# Pinscape_Pico_Expansion_Board_-_DIY_Frie.net
KiCad netlist of a schematic drawn in EAGLE
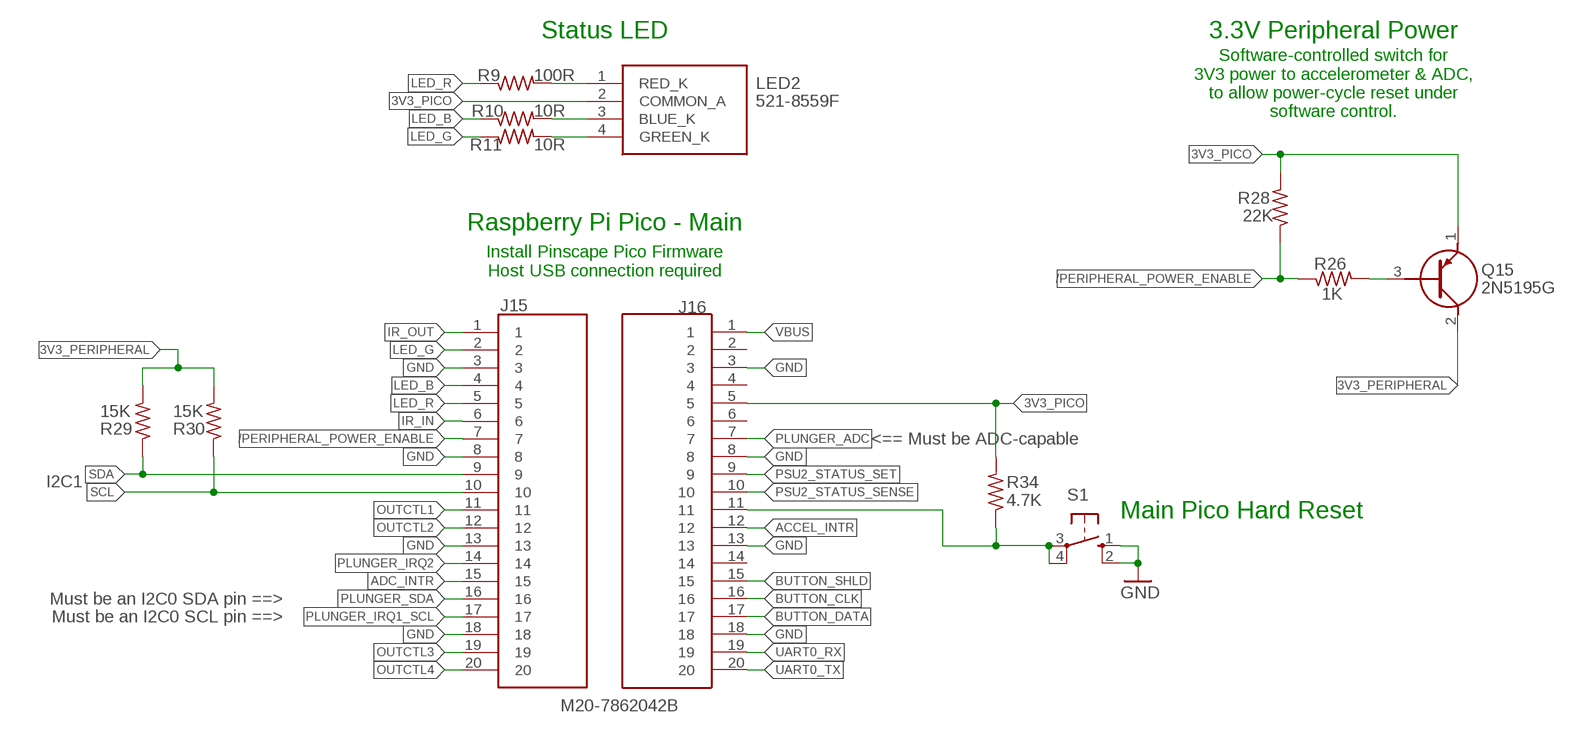
[diagram p0: schematic, sheet 1]
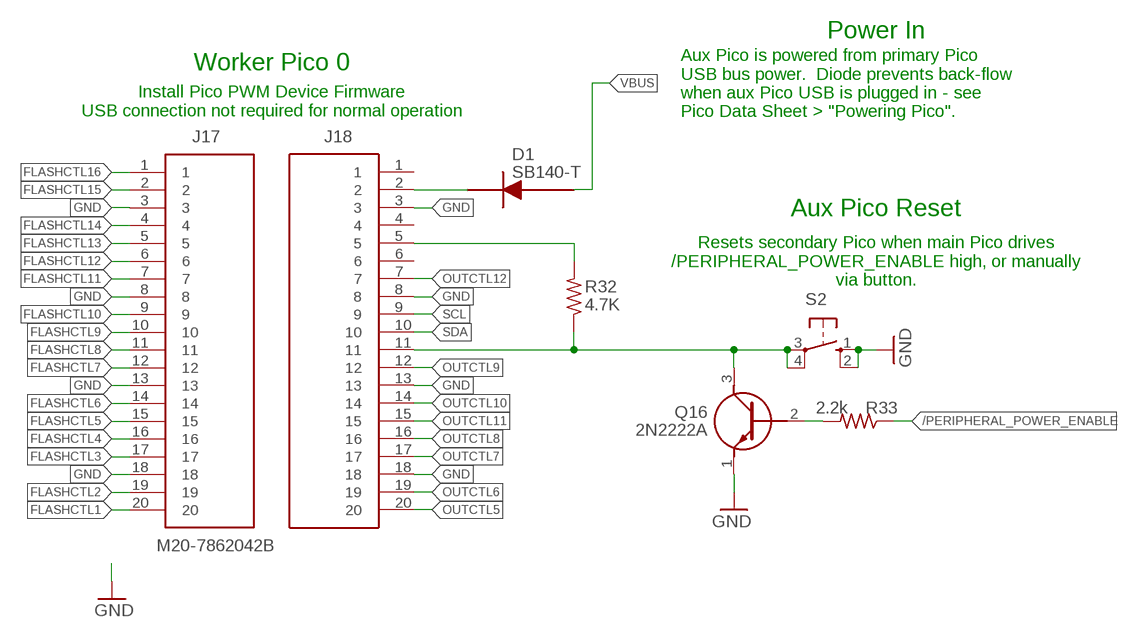
[diagram p1: schematic, sheet 2]
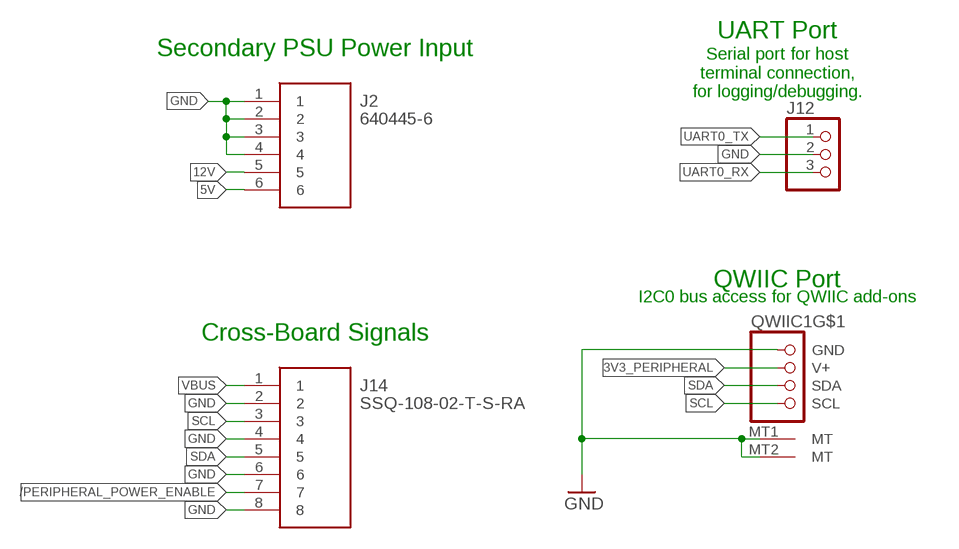
[diagram p2: schematic, sheet 3]
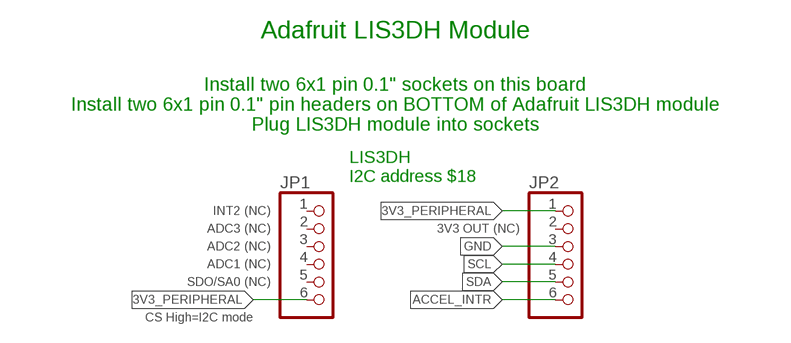
[diagram p3: schematic, sheet 4]
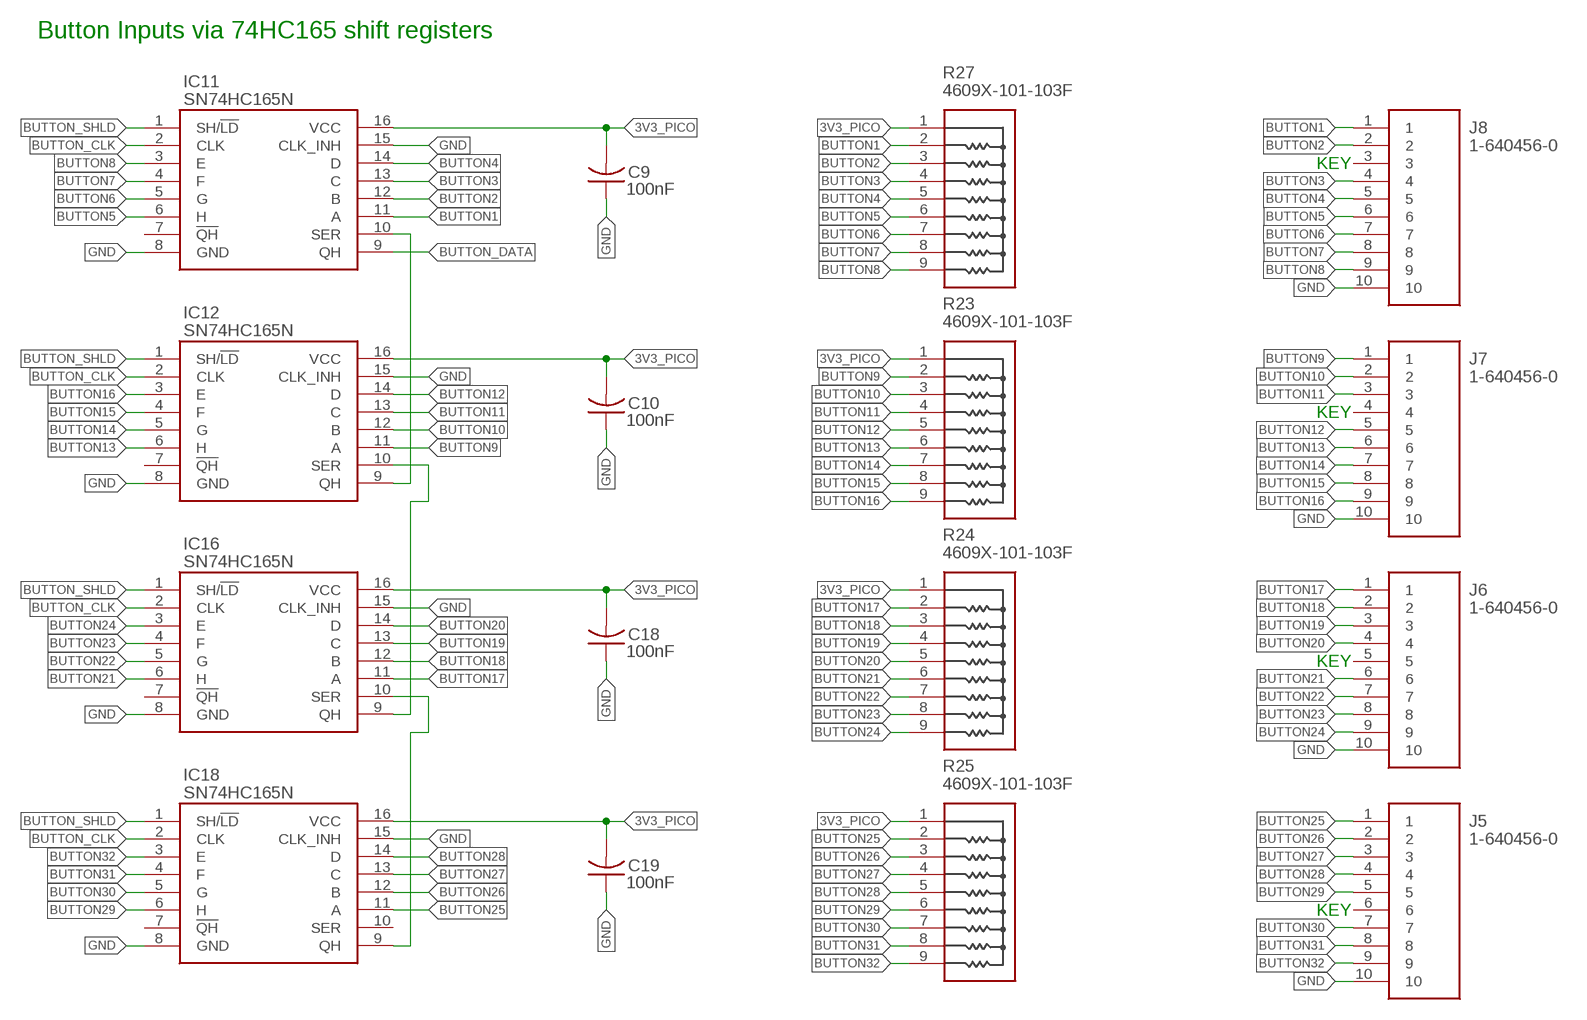
[diagram p4: schematic, sheet 5]
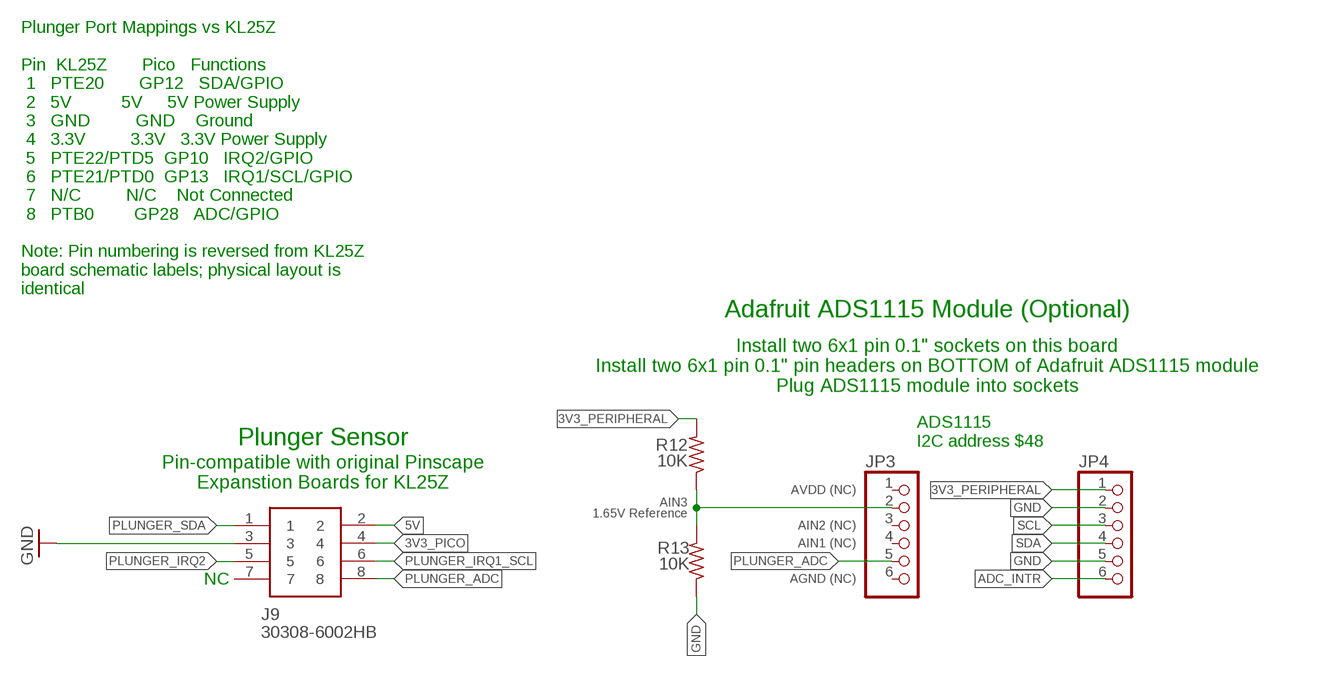
[diagram p5: schematic, sheet 6]
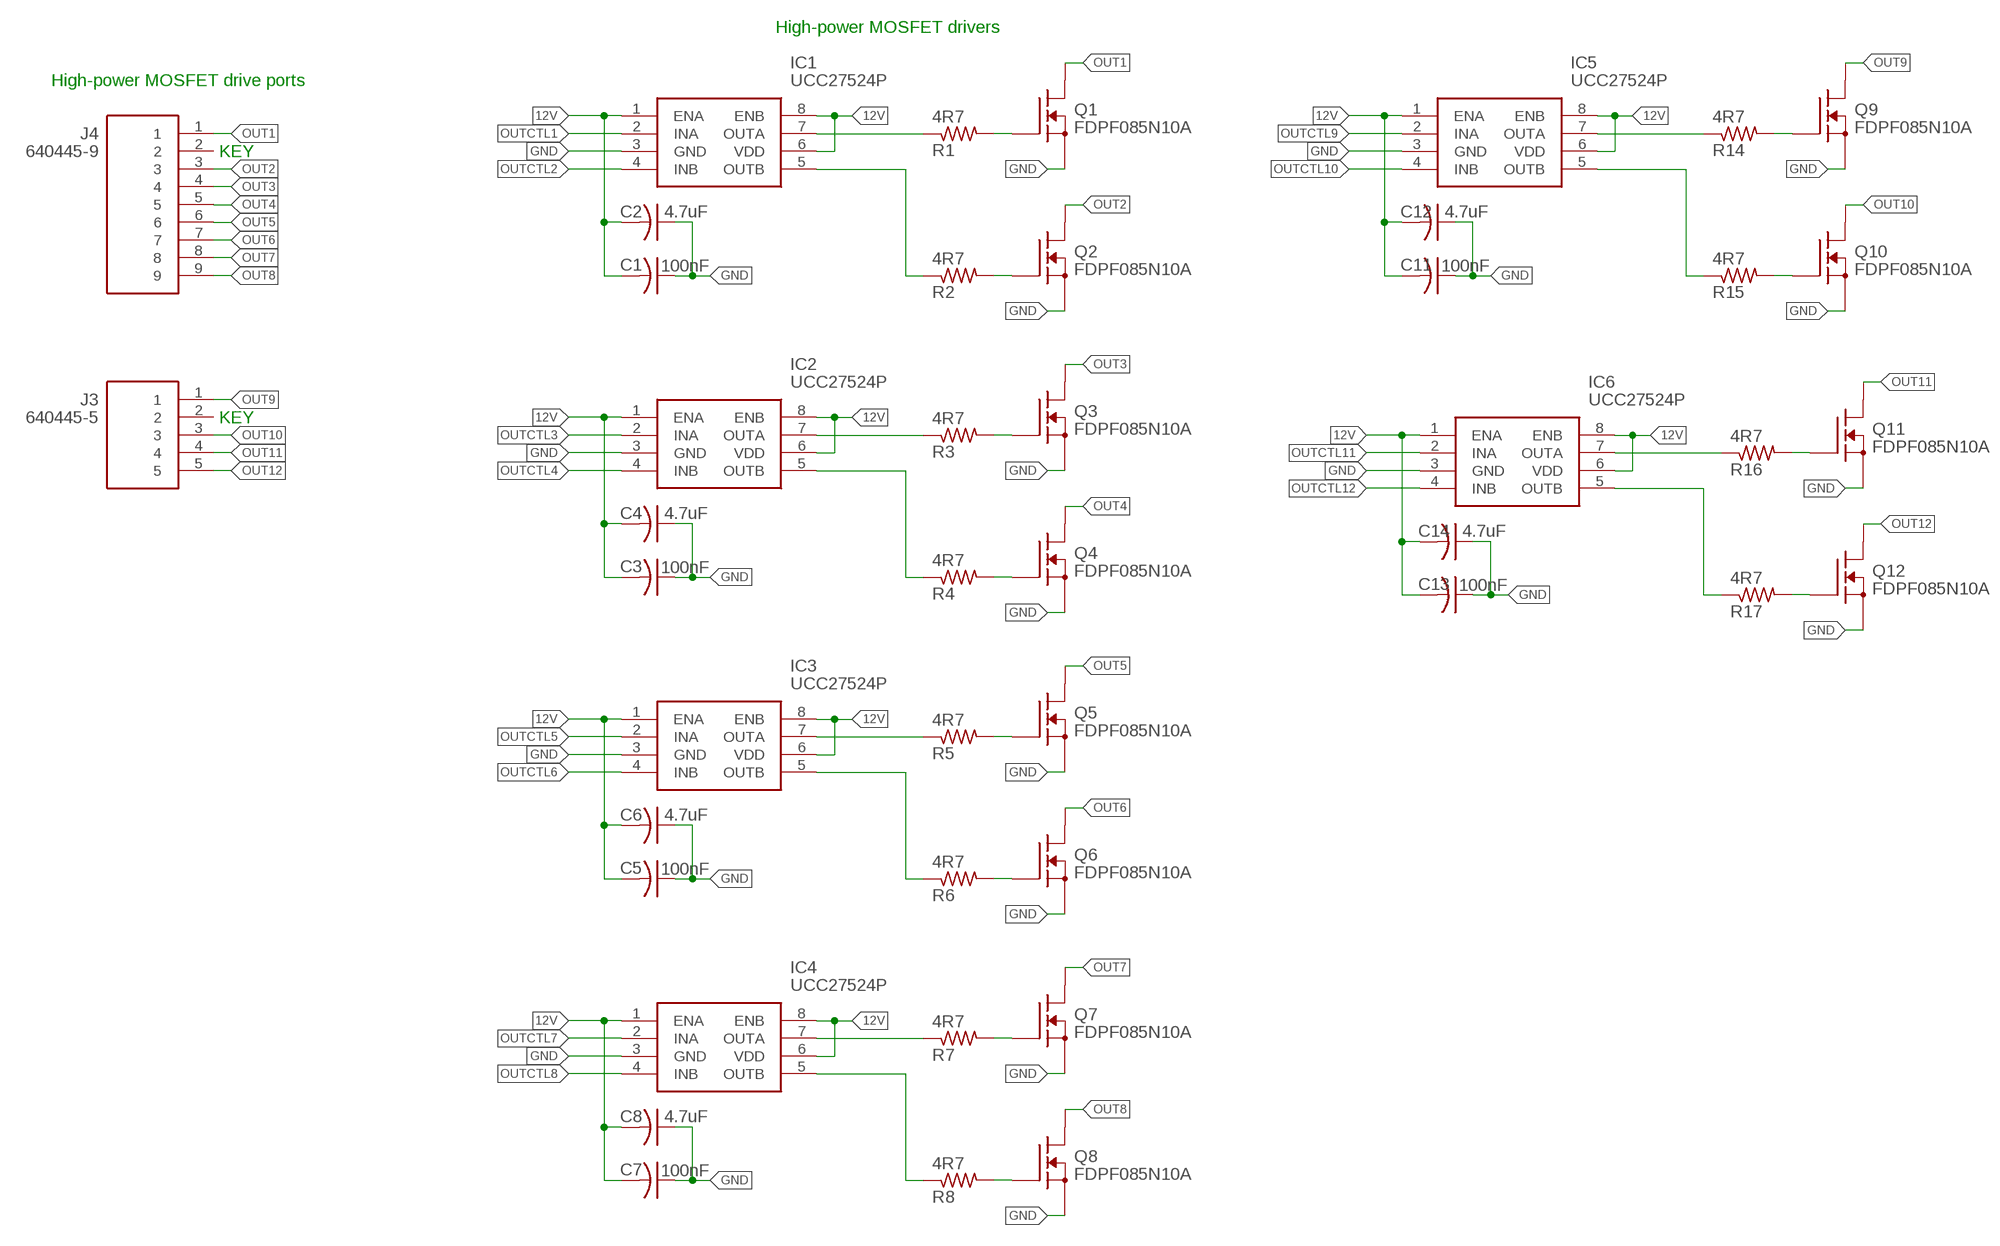
[diagram p6: schematic, sheet 7]
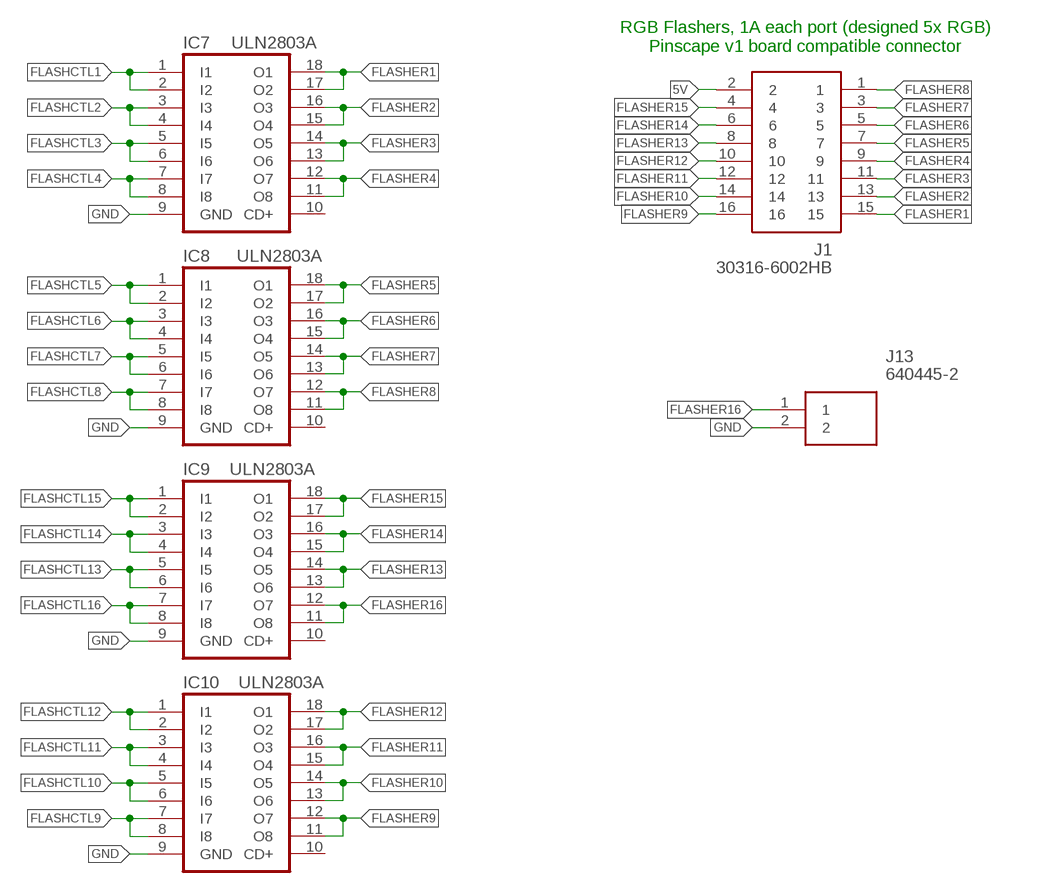
[diagram p7: schematic, sheet 8]
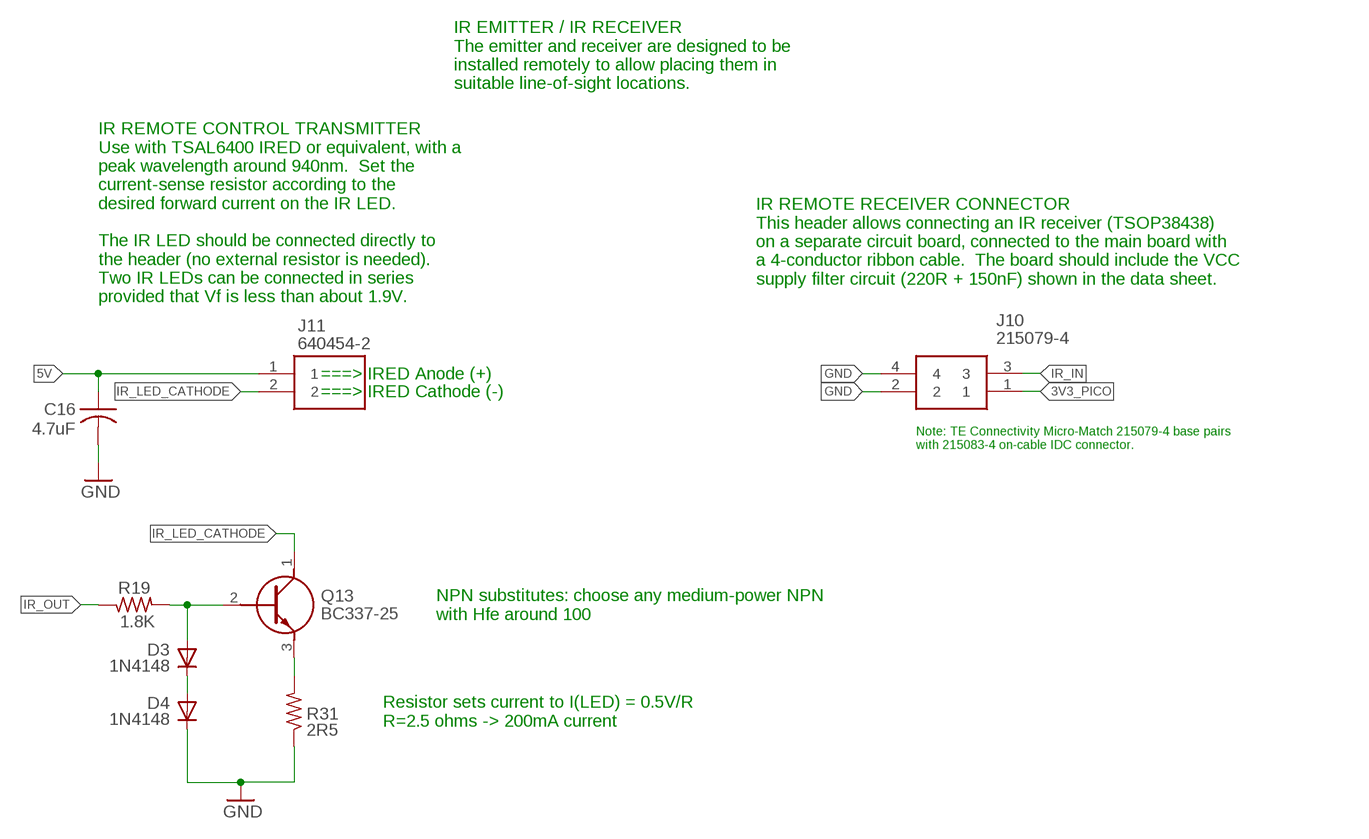
[diagram p8: schematic, sheet 9]
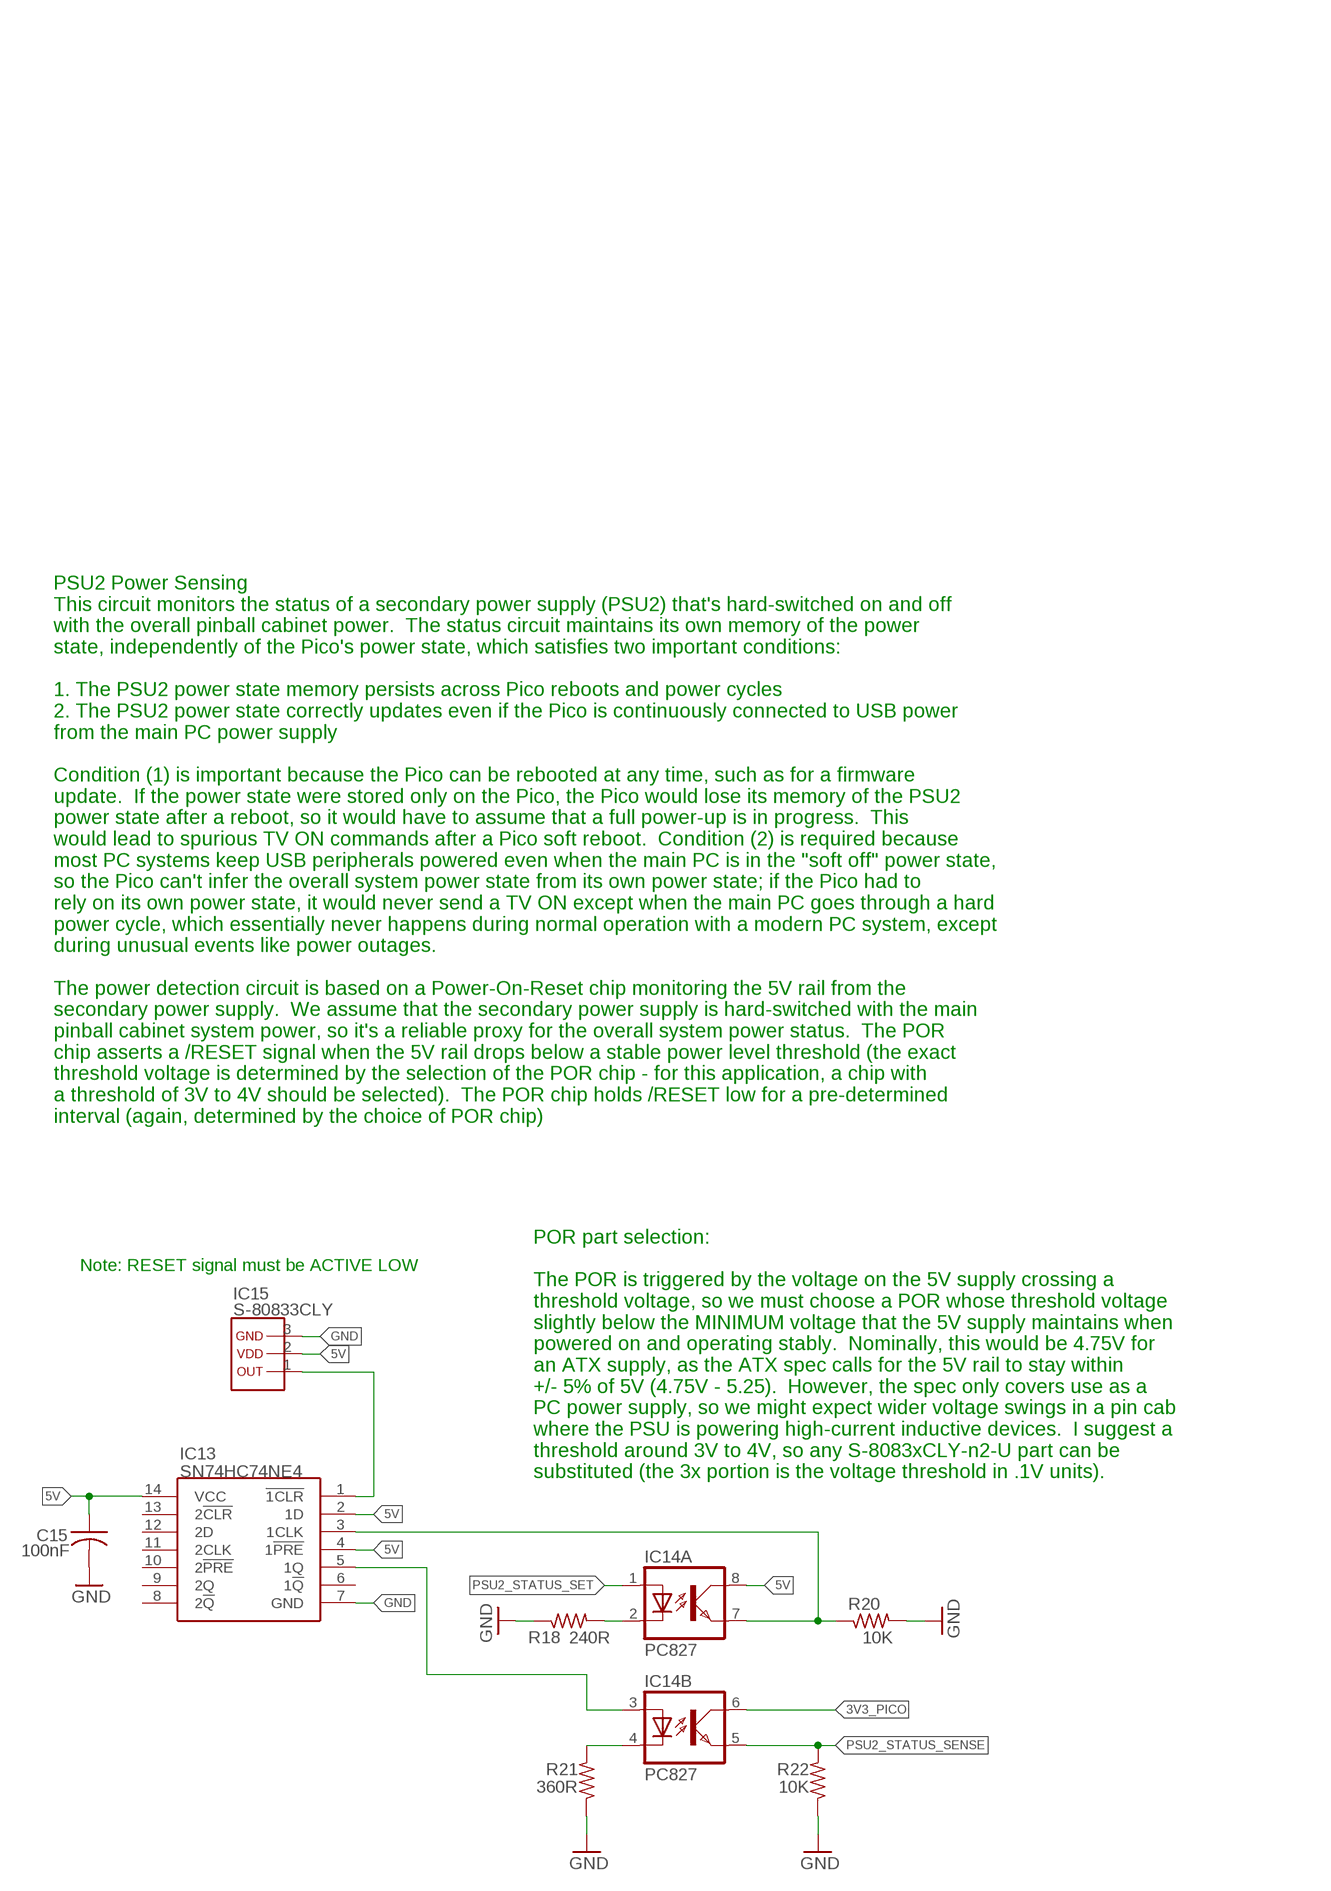
[diagram p9: schematic, sheet 10]
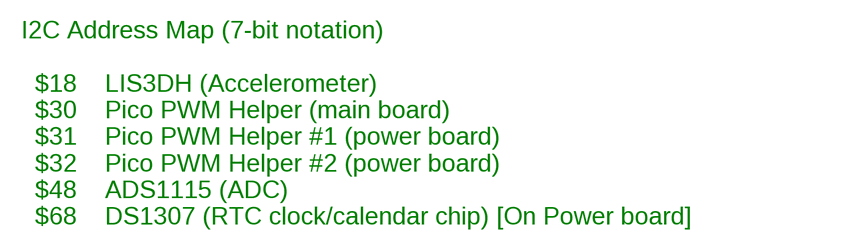
[diagram p10: schematic, sheet 11]

(export (version "E")
  (design (tool "Eeschema 10.0.6"))
  (components
    (comp (ref "JP1")
      (value "PINHD-1X6")
      (footprint "eagle-import:1X06")
      (libsource (lib "eagle-import") (part "PINHD-1X6"))
    )
    (comp (ref "JP2")
      (value "PINHD-1X6")
      (footprint "eagle-import:1X06")
      (libsource (lib "eagle-import") (part "PINHD-1X6"))
    )
    (comp (ref "J15")
      (value "M20-7862042B")
      (footprint "eagle-import:M20-7862042-B")
      (libsource (lib "eagle-import") (part "M20-7862042B"))
    )
    (comp (ref "J16")
      (value "M20-7862042B")
      (footprint "eagle-import:M20-7862042-B")
      (libsource (lib "eagle-import") (part "M20-7862042B"))
    )
    (comp (ref "LED2")
      (value "521-8559F")
      (footprint "eagle-import:5218559F")
      (fields (field (name "MOUSER_PART_NUMBER") "645-5218559F"))
      (libsource (lib "eagle-import") (part "521-8559F"))
    )
    (comp (ref "Q15")
      (value "2N5195G")
      (footprint "eagle-import:TO229P300X760X1364-3P")
      (fields (field (name "MOUSER_PART_NUMBER") "863-2N5195G"))
      (libsource (lib "eagle-import") (part "2N5195G"))
    )
    (comp (ref "R9")
      (value "100R")
      (footprint "eagle-import:0204_7")
      (fields (field (name "PARTNO") "660-MFS1/4DCT52R47R0"))
      (libsource (lib "eagle-import") (part "R-US_0204/7"))
    )
    (comp (ref "R10")
      (value "10R")
      (footprint "eagle-import:0204_7")
      (fields (field (name "PARTNO") "660-MFS1/4DCT52R47R0"))
      (libsource (lib "eagle-import") (part "R-US_0204/7"))
    )
    (comp (ref "R11")
      (value "10R")
      (footprint "eagle-import:0204_7")
      (fields (field (name "PARTNO") "660-MFS1/4DCT52R47R0"))
      (libsource (lib "eagle-import") (part "R-US_0204/7"))
    )
    (comp (ref "R26")
      (value "1K")
      (footprint "eagle-import:0204_7")
      (fields (field (name "PARTNO") "660-MFS1/4DCT52R47R0"))
      (libsource (lib "eagle-import") (part "R-US_0204/7"))
    )
    (comp (ref "R28")
      (value "22K")
      (footprint "eagle-import:0204_7")
      (fields (field (name "PARTNO") "660-MFS1/4DCT52R47R0"))
      (libsource (lib "eagle-import") (part "R-US_0204/7"))
    )
    (comp (ref "R29")
      (value "15K")
      (footprint "eagle-import:0204_7")
      (fields (field (name "PARTNO") "660-MFS1/4DCT52R47R0"))
      (libsource (lib "eagle-import") (part "R-US_0204/7"))
    )
    (comp (ref "R30")
      (value "15K")
      (footprint "eagle-import:0204_7")
      (fields (field (name "PARTNO") "660-MFS1/4DCT52R47R0"))
      (libsource (lib "eagle-import") (part "R-US_0204/7"))
    )
    (comp (ref "R34")
      (value "4.7K")
      (footprint "eagle-import:0204_7")
      (fields (field (name "PARTNO") "660-MFS1/4DCT52R47R0"))
      (libsource (lib "eagle-import") (part "R-US_0204/7"))
    )
    (comp (ref "S1")
      (value "10-XX")
      (footprint "eagle-import:B3F-10XX")
      (fields (field (name "MPN") "B3F-1000"))
      (libsource (lib "eagle-import") (part "10-XX"))
    )
    (comp (ref "J2")
      (value "640445-6")
      (footprint "eagle-import:SHDR6W183P0X396_1X6_2377X762X1")
      (fields (field (name "MOUSER_PART_NUMBER") "571-6404456"))
      (libsource (lib "eagle-import") (part "640445-6"))
    )
    (comp (ref "J12")
      (value "PINHD-1X3")
      (footprint "eagle-import:1X03")
      (libsource (lib "eagle-import") (part "PINHD-1X3"))
    )
    (comp (ref "J14")
      (value "SSQ-108-02-T-S-RA")
      (footprint "eagle-import:RHDRRA8W64P254_1X8_2083X851X24")
      (fields (field (name "MOUSER_PART_NUMBER") "200-SSQ10802TSRA"))
      (libsource (lib "eagle-import") (part "SSQ-108-02-T-S-RA"))
    )
    (comp (ref "QWIIC1")
      (value "QWIIC")
      (footprint "eagle-import:JST_SH4")
      (libsource (lib "eagle-import") (part "STEMMA_I2C_QT"))
    )
    (comp (ref "D1")
      (value "SB140-T")
      (footprint "eagle-import:DIOAD1408W86L464D236")
      (fields (field (name "MOUSER_PART_NUMBER") "621-SB140-T"))
      (libsource (lib "eagle-import") (part "SB140-T"))
    )
    (comp (ref "J17")
      (value "M20-7862042B")
      (footprint "eagle-import:M20-7862042-B")
      (libsource (lib "eagle-import") (part "M20-7862042B"))
    )
    (comp (ref "J18")
      (value "M20-7862042B")
      (footprint "eagle-import:M20-7862042-B")
      (libsource (lib "eagle-import") (part "M20-7862042B"))
    )
    (comp (ref "Q16")
      (value "2N2222A")
      (footprint "eagle-import:2N2222A")
      (fields (field (name "MOUSER_PART_NUMBER") "637-2N2222A"))
      (libsource (lib "eagle-import") (part "2N2222A"))
    )
    (comp (ref "R32")
      (value "4.7K")
      (footprint "eagle-import:0204_7")
      (fields (field (name "PARTNO") "660-MFS1/4DCT52R47R0"))
      (libsource (lib "eagle-import") (part "R-US_0204/7"))
    )
    (comp (ref "R33")
      (value "2.2k")
      (footprint "eagle-import:0204_7")
      (fields (field (name "PARTNO") "660-MFS1/4DCT52R47R0"))
      (libsource (lib "eagle-import") (part "R-US_0204/7"))
    )
    (comp (ref "S2")
      (value "10-XX")
      (footprint "eagle-import:B3F-10XX")
      (fields (field (name "MPN") "B3F-1000"))
      (libsource (lib "eagle-import") (part "10-XX"))
    )
    (comp (ref "IC7")
      (value "ULN2803A")
      (footprint "eagle-import:DIL18")
      (libsource (lib "eagle-import") (part "ULN2803A"))
    )
    (comp (ref "IC8")
      (value "ULN2803A")
      (footprint "eagle-import:DIL18")
      (libsource (lib "eagle-import") (part "ULN2803A"))
    )
    (comp (ref "IC9")
      (value "ULN2803A")
      (footprint "eagle-import:DIL18")
      (libsource (lib "eagle-import") (part "ULN2803A"))
    )
    (comp (ref "IC10")
      (value "ULN2803A")
      (footprint "eagle-import:DIL18")
      (libsource (lib "eagle-import") (part "ULN2803A"))
    )
    (comp (ref "J1")
      (value "30316-6002HB")
      (footprint "eagle-import:3M-30316-6002HB")
      (fields (field (name "MOUSER_PART_NUMBER") "517-30316-6002"))
      (libsource (lib "eagle-import") (part "30316-6002HB"))
    )
    (comp (ref "J13")
      (value "640445-2")
      (footprint "eagle-import:SHDR2W117P0X396_1X2_792X762X11")
      (fields (field (name "MOUSER_PART_NUMBER") "5716404452"))
      (libsource (lib "eagle-import") (part "640445-2"))
    )
    (comp (ref "C1")
      (value "100nF")
      (footprint "eagle-import:C025-024X044")
      (fields (field (name "PARTNO") "21RZ310-RC"))
      (libsource (lib "eagle-import") (part "C-US025-024X044"))
    )
    (comp (ref "C2")
      (value "4.7uF")
      (footprint "eagle-import:C025-024X044")
      (fields (field (name "PARTNO") "810-FG14X5R1H475KRT0"))
      (libsource (lib "eagle-import") (part "C-US025-024X044"))
    )
    (comp (ref "C3")
      (value "100nF")
      (footprint "eagle-import:C025-024X044")
      (fields (field (name "PARTNO") "21RZ310-RC"))
      (libsource (lib "eagle-import") (part "C-US025-024X044"))
    )
    (comp (ref "C4")
      (value "4.7uF")
      (footprint "eagle-import:C025-024X044")
      (fields (field (name "PARTNO") "810-FG14X5R1H475KRT0"))
      (libsource (lib "eagle-import") (part "C-US025-024X044"))
    )
    (comp (ref "C5")
      (value "100nF")
      (footprint "eagle-import:C025-024X044")
      (fields (field (name "PARTNO") "21RZ310-RC"))
      (libsource (lib "eagle-import") (part "C-US025-024X044"))
    )
    (comp (ref "C6")
      (value "4.7uF")
      (footprint "eagle-import:C025-024X044")
      (fields (field (name "PARTNO") "810-FG14X5R1H475KRT0"))
      (libsource (lib "eagle-import") (part "C-US025-024X044"))
    )
    (comp (ref "C7")
      (value "100nF")
      (footprint "eagle-import:C025-024X044")
      (fields (field (name "PARTNO") "21RZ310-RC"))
      (libsource (lib "eagle-import") (part "C-US025-024X044"))
    )
    (comp (ref "C8")
      (value "4.7uF")
      (footprint "eagle-import:C025-024X044")
      (fields (field (name "PARTNO") "810-FG14X5R1H475KRT0"))
      (libsource (lib "eagle-import") (part "C-US025-024X044"))
    )
    (comp (ref "C11")
      (value "100nF")
      (footprint "eagle-import:C025-024X044")
      (fields (field (name "PARTNO") "21RZ310-RC"))
      (libsource (lib "eagle-import") (part "C-US025-024X044"))
    )
    (comp (ref "C12")
      (value "4.7uF")
      (footprint "eagle-import:C025-024X044")
      (fields (field (name "PARTNO") "810-FG14X5R1H475KRT0"))
      (libsource (lib "eagle-import") (part "C-US025-024X044"))
    )
    (comp (ref "C13")
      (value "100nF")
      (footprint "eagle-import:C025-024X044")
      (fields (field (name "PARTNO") "21RZ310-RC"))
      (libsource (lib "eagle-import") (part "C-US025-024X044"))
    )
    (comp (ref "C14")
      (value "4.7uF")
      (footprint "eagle-import:C025-024X044")
      (fields (field (name "PARTNO") "810-FG14X5R1H475KRT0"))
      (libsource (lib "eagle-import") (part "C-US025-024X044"))
    )
    (comp (ref "IC1")
      (value "UCC27524P")
      (footprint "eagle-import:DIP794W53P254L959H508Q8N")
      (fields (field (name "MOUSER_PART_NUMBER") "595-UCC27524P"))
      (libsource (lib "eagle-import") (part "UCC27524P"))
    )
    (comp (ref "IC2")
      (value "UCC27524P")
      (footprint "eagle-import:DIP794W53P254L959H508Q8N")
      (fields (field (name "MOUSER_PART_NUMBER") "595-UCC27524P"))
      (libsource (lib "eagle-import") (part "UCC27524P"))
    )
    (comp (ref "IC3")
      (value "UCC27524P")
      (footprint "eagle-import:DIP794W53P254L959H508Q8N")
      (fields (field (name "MOUSER_PART_NUMBER") "595-UCC27524P"))
      (libsource (lib "eagle-import") (part "UCC27524P"))
    )
    (comp (ref "IC4")
      (value "UCC27524P")
      (footprint "eagle-import:DIP794W53P254L959H508Q8N")
      (fields (field (name "MOUSER_PART_NUMBER") "595-UCC27524P"))
      (libsource (lib "eagle-import") (part "UCC27524P"))
    )
    (comp (ref "IC5")
      (value "UCC27524P")
      (footprint "eagle-import:DIP794W53P254L959H508Q8N")
      (fields (field (name "MOUSER_PART_NUMBER") "595-UCC27524P"))
      (libsource (lib "eagle-import") (part "UCC27524P"))
    )
    (comp (ref "IC6")
      (value "UCC27524P")
      (footprint "eagle-import:DIP794W53P254L959H508Q8N")
      (fields (field (name "MOUSER_PART_NUMBER") "595-UCC27524P"))
      (libsource (lib "eagle-import") (part "UCC27524P"))
    )
    (comp (ref "J3")
      (value "640445-5")
      (footprint "eagle-import:HDRV5W117P0X396_1X5_1981X762X1")
      (fields (field (name "MOUSER_PART_NUMBER") "571-640445-5"))
      (libsource (lib "eagle-import") (part "640445-5"))
    )
    (comp (ref "J4")
      (value "640445-9")
      (footprint "eagle-import:SHDR9W117P0X396_1X9_3566X762X1")
      (fields (field (name "MOUSER_PART_NUMBER") "571-6404459"))
      (libsource (lib "eagle-import") (part "640445-9"))
    )
    (comp (ref "Q1")
      (value "FDPF085N10A")
      (footprint "eagle-import:TO220BV")
      (fields (field (name "PARTNO") "FDPF085N10A"))
      (libsource (lib "eagle-import") (part "BUK7575-55A"))
    )
    (comp (ref "Q2")
      (value "FDPF085N10A")
      (footprint "eagle-import:TO220BV")
      (fields (field (name "PARTNO") "FDPF085N10A"))
      (libsource (lib "eagle-import") (part "BUK7575-55A"))
    )
    (comp (ref "Q3")
      (value "FDPF085N10A")
      (footprint "eagle-import:TO220BV")
      (fields (field (name "PARTNO") "FDPF085N10A"))
      (libsource (lib "eagle-import") (part "BUK7575-55A"))
    )
    (comp (ref "Q4")
      (value "FDPF085N10A")
      (footprint "eagle-import:TO220BV")
      (fields (field (name "PARTNO") "FDPF085N10A"))
      (libsource (lib "eagle-import") (part "BUK7575-55A"))
    )
    (comp (ref "Q5")
      (value "FDPF085N10A")
      (footprint "eagle-import:TO220BV")
      (fields (field (name "PARTNO") "FDPF085N10A"))
      (libsource (lib "eagle-import") (part "BUK7575-55A"))
    )
    (comp (ref "Q6")
      (value "FDPF085N10A")
      (footprint "eagle-import:TO220BV")
      (fields (field (name "PARTNO") "FDPF085N10A"))
      (libsource (lib "eagle-import") (part "BUK7575-55A"))
    )
    (comp (ref "Q7")
      (value "FDPF085N10A")
      (footprint "eagle-import:TO220BV")
      (fields (field (name "PARTNO") "FDPF085N10A"))
      (libsource (lib "eagle-import") (part "BUK7575-55A"))
    )
    (comp (ref "Q8")
      (value "FDPF085N10A")
      (footprint "eagle-import:TO220BV")
      (fields (field (name "PARTNO") "FDPF085N10A"))
      (libsource (lib "eagle-import") (part "BUK7575-55A"))
    )
    (comp (ref "Q9")
      (value "FDPF085N10A")
      (footprint "eagle-import:TO220BV")
      (fields (field (name "PARTNO") "FDPF085N10A"))
      (libsource (lib "eagle-import") (part "BUK7575-55A"))
    )
    (comp (ref "Q10")
      (value "FDPF085N10A")
      (footprint "eagle-import:TO220BV")
      (fields (field (name "PARTNO") "FDPF085N10A"))
      (libsource (lib "eagle-import") (part "BUK7575-55A"))
    )
    (comp (ref "Q11")
      (value "FDPF085N10A")
      (footprint "eagle-import:TO220BV")
      (fields (field (name "PARTNO") "FDPF085N10A"))
      (libsource (lib "eagle-import") (part "BUK7575-55A"))
    )
    (comp (ref "Q12")
      (value "FDPF085N10A")
      (footprint "eagle-import:TO220BV")
      (fields (field (name "PARTNO") "FDPF085N10A"))
      (libsource (lib "eagle-import") (part "BUK7575-55A"))
    )
    (comp (ref "R1")
      (value "4R7")
      (footprint "eagle-import:0204_5")
      (fields (field (name "PARTNO") "660-MFS1/4DCT52R47R0"))
      (libsource (lib "eagle-import") (part "R-US_0204/5"))
    )
    (comp (ref "R2")
      (value "4R7")
      (footprint "eagle-import:0204_5")
      (fields (field (name "PARTNO") "660-MFS1/4DCT52R47R0"))
      (libsource (lib "eagle-import") (part "R-US_0204/5"))
    )
    (comp (ref "R3")
      (value "4R7")
      (footprint "eagle-import:0204_5")
      (fields (field (name "PARTNO") "660-MFS1/4DCT52R47R0"))
      (libsource (lib "eagle-import") (part "R-US_0204/5"))
    )
    (comp (ref "R4")
      (value "4R7")
      (footprint "eagle-import:0204_5")
      (fields (field (name "PARTNO") "660-MFS1/4DCT52R47R0"))
      (libsource (lib "eagle-import") (part "R-US_0204/5"))
    )
    (comp (ref "R5")
      (value "4R7")
      (footprint "eagle-import:0204_5")
      (fields (field (name "PARTNO") "660-MFS1/4DCT52R47R0"))
      (libsource (lib "eagle-import") (part "R-US_0204/5"))
    )
    (comp (ref "R6")
      (value "4R7")
      (footprint "eagle-import:0204_5")
      (fields (field (name "PARTNO") "660-MFS1/4DCT52R47R0"))
      (libsource (lib "eagle-import") (part "R-US_0204/5"))
    )
    (comp (ref "R7")
      (value "4R7")
      (footprint "eagle-import:0204_5")
      (fields (field (name "PARTNO") "660-MFS1/4DCT52R47R0"))
      (libsource (lib "eagle-import") (part "R-US_0204/5"))
    )
    (comp (ref "R8")
      (value "4R7")
      (footprint "eagle-import:0204_5")
      (fields (field (name "PARTNO") "660-MFS1/4DCT52R47R0"))
      (libsource (lib "eagle-import") (part "R-US_0204/5"))
    )
    (comp (ref "R14")
      (value "4R7")
      (footprint "eagle-import:0204_5")
      (fields (field (name "PARTNO") "660-MFS1/4DCT52R47R0"))
      (libsource (lib "eagle-import") (part "R-US_0204/5"))
    )
    (comp (ref "R15")
      (value "4R7")
      (footprint "eagle-import:0204_5")
      (fields (field (name "PARTNO") "660-MFS1/4DCT52R47R0"))
      (libsource (lib "eagle-import") (part "R-US_0204/5"))
    )
    (comp (ref "R16")
      (value "4R7")
      (footprint "eagle-import:0204_5")
      (fields (field (name "PARTNO") "660-MFS1/4DCT52R47R0"))
      (libsource (lib "eagle-import") (part "R-US_0204/5"))
    )
    (comp (ref "R17")
      (value "4R7")
      (footprint "eagle-import:0204_5")
      (fields (field (name "PARTNO") "660-MFS1/4DCT52R47R0"))
      (libsource (lib "eagle-import") (part "R-US_0204/5"))
    )
    (comp (ref "C9")
      (value "100nF")
      (footprint "eagle-import:C025-024X044")
      (fields (field (name "PARTNO") "21RZ310-RC"))
      (libsource (lib "eagle-import") (part "C-US025-024X044"))
    )
    (comp (ref "C10")
      (value "100nF")
      (footprint "eagle-import:C025-024X044")
      (fields (field (name "PARTNO") "21RZ310-RC"))
      (libsource (lib "eagle-import") (part "C-US025-024X044"))
    )
    (comp (ref "C18")
      (value "100nF")
      (footprint "eagle-import:C025-024X044")
      (fields (field (name "PARTNO") "21RZ310-RC"))
      (libsource (lib "eagle-import") (part "C-US025-024X044"))
    )
    (comp (ref "C19")
      (value "100nF")
      (footprint "eagle-import:C025-024X044")
      (fields (field (name "PARTNO") "21RZ310-RC"))
      (libsource (lib "eagle-import") (part "C-US025-024X044"))
    )
    (comp (ref "IC11")
      (value "SN74HC165N")
      (footprint "eagle-import:DIP794W53P254L1930H508Q16N")
      (fields (field (name "MOUSER_PART_NUMBER") "595-SN74HC165N"))
      (libsource (lib "eagle-import") (part "SN74HC165N"))
    )
    (comp (ref "IC12")
      (value "SN74HC165N")
      (footprint "eagle-import:DIP794W53P254L1930H508Q16N")
      (fields (field (name "MOUSER_PART_NUMBER") "595-SN74HC165N"))
      (libsource (lib "eagle-import") (part "SN74HC165N"))
    )
    (comp (ref "IC16")
      (value "SN74HC165N")
      (footprint "eagle-import:DIP794W53P254L1930H508Q16N")
      (fields (field (name "MOUSER_PART_NUMBER") "595-SN74HC165N"))
      (libsource (lib "eagle-import") (part "SN74HC165N"))
    )
    (comp (ref "IC18")
      (value "SN74HC165N")
      (footprint "eagle-import:DIP794W53P254L1930H508Q16N")
      (fields (field (name "MOUSER_PART_NUMBER") "595-SN74HC165N"))
      (libsource (lib "eagle-import") (part "SN74HC165N"))
    )
    (comp (ref "J5")
      (value "1-640456-0")
      (footprint "eagle-import:SHDR10W66P0X254_1X10_2540X572X")
      (fields (field (name "MOUSER_PART_NUMBER") "571-16404560"))
      (libsource (lib "eagle-import") (part "1-640456-0"))
    )
    (comp (ref "J6")
      (value "1-640456-0")
      (footprint "eagle-import:SHDR10W66P0X254_1X10_2540X572X")
      (fields (field (name "MOUSER_PART_NUMBER") "571-16404560"))
      (libsource (lib "eagle-import") (part "1-640456-0"))
    )
    (comp (ref "J7")
      (value "1-640456-0")
      (footprint "eagle-import:SHDR10W66P0X254_1X10_2540X572X")
      (fields (field (name "MOUSER_PART_NUMBER") "571-16404560"))
      (libsource (lib "eagle-import") (part "1-640456-0"))
    )
    (comp (ref "J8")
      (value "1-640456-0")
      (footprint "eagle-import:SHDR10W66P0X254_1X10_2540X572X")
      (fields (field (name "MOUSER_PART_NUMBER") "571-16404560"))
      (libsource (lib "eagle-import") (part "1-640456-0"))
    )
    (comp (ref "R23")
      (value "4609X-101-103F")
      (footprint "eagle-import:4609X")
      (fields
        (field (name "MANUFACTURER_PART_NUMBER") "4609X-101-122LF")
        (field (name "MOUSER_PART_NUMBER") "652-4609X-1LF-1.2K")
      )
      (libsource (lib "eagle-import") (part "4609X-101-122LF"))
    )
    (comp (ref "R24")
      (value "4609X-101-103F")
      (footprint "eagle-import:4609X")
      (fields
        (field (name "MANUFACTURER_PART_NUMBER") "4609X-101-122LF")
        (field (name "MOUSER_PART_NUMBER") "652-4609X-1LF-1.2K")
      )
      (libsource (lib "eagle-import") (part "4609X-101-122LF"))
    )
    (comp (ref "R25")
      (value "4609X-101-103F")
      (footprint "eagle-import:4609X")
      (fields
        (field (name "MANUFACTURER_PART_NUMBER") "4609X-101-122LF")
        (field (name "MOUSER_PART_NUMBER") "652-4609X-1LF-1.2K")
      )
      (libsource (lib "eagle-import") (part "4609X-101-122LF"))
    )
    (comp (ref "R27")
      (value "4609X-101-103F")
      (footprint "eagle-import:4609X")
      (fields
        (field (name "MANUFACTURER_PART_NUMBER") "4609X-101-122LF")
        (field (name "MOUSER_PART_NUMBER") "652-4609X-1LF-1.2K")
      )
      (libsource (lib "eagle-import") (part "4609X-101-122LF"))
    )
    (comp (ref "J9")
      (value "30308-6002HB")
      (footprint "eagle-import:SHDR8W69P254_2X4_1780X878X955P")
      (libsource (lib "eagle-import") (part "30308-6002HB"))
    )
    (comp (ref "JP3")
      (value "PINHD-1X6")
      (footprint "eagle-import:1X06")
      (libsource (lib "eagle-import") (part "PINHD-1X6"))
    )
    (comp (ref "JP4")
      (value "PINHD-1X6")
      (footprint "eagle-import:1X06")
      (libsource (lib "eagle-import") (part "PINHD-1X6"))
    )
    (comp (ref "R12")
      (value "10K")
      (footprint "eagle-import:0204_7")
      (fields (field (name "PARTNO") "660-MFS1/4DCT52R47R0"))
      (libsource (lib "eagle-import") (part "R-US_0204/7"))
    )
    (comp (ref "R13")
      (value "10K")
      (footprint "eagle-import:0204_7")
      (fields (field (name "PARTNO") "660-MFS1/4DCT52R47R0"))
      (libsource (lib "eagle-import") (part "R-US_0204/7"))
    )
    (comp (ref "C15")
      (value "100nF")
      (footprint "eagle-import:C025-024X044")
      (fields (field (name "PARTNO") "21RZ310-RC"))
      (libsource (lib "eagle-import") (part "C-US025-024X044"))
    )
    (comp (ref "IC13")
      (value "SN74HC74NE4")
      (footprint "eagle-import:DIP794W53P254L1930H508Q14N")
      (fields (field (name "MOUSER_PART_NUMBER") "595-SN74HC74NE4"))
      (libsource (lib "eagle-import") (part "SN74HC74NE4"))
    )
    (comp (ref "IC14")
      (value "PC827")
      (footprint "eagle-import:DIL08")
      (libsource (lib "eagle-import") (part "PC827"))
    )
    (comp (ref "IC15")
      (value "S-80833CLY")
      (footprint "eagle-import:TO-92_(TO-226)")
      (libsource (lib "eagle-import") (part "S-80833CLY-B2-UTO92"))
    )
    (comp (ref "R18")
      (value "240R")
      (footprint "eagle-import:0204_7")
      (fields (field (name "PARTNO") "660-MFS1/4DCT52R47R0"))
      (libsource (lib "eagle-import") (part "R-US_0204/7"))
    )
    (comp (ref "R20")
      (value "10K")
      (footprint "eagle-import:0204_7")
      (fields (field (name "PARTNO") "660-MFS1/4DCT52R47R0"))
      (libsource (lib "eagle-import") (part "R-US_0204/7"))
    )
    (comp (ref "R21")
      (value "360R")
      (footprint "eagle-import:0204_7")
      (fields (field (name "PARTNO") "660-MFS1/4DCT52R47R0"))
      (libsource (lib "eagle-import") (part "R-US_0204/7"))
    )
    (comp (ref "R22")
      (value "10K")
      (footprint "eagle-import:0204_7")
      (fields (field (name "PARTNO") "660-MFS1/4DCT52R47R0"))
      (libsource (lib "eagle-import") (part "R-US_0204/7"))
    )
    (comp (ref "C16")
      (value "4.7uF")
      (footprint "eagle-import:C025-024X044")
      (fields (field (name "PARTNO") "810-FG14X5R1H475KRT0"))
      (libsource (lib "eagle-import") (part "C-US025-024X044"))
    )
    (comp (ref "D3")
      (value "1N4148")
      (footprint "eagle-import:DO35-7")
      (libsource (lib "eagle-import") (part "1N4148DO35-7"))
    )
    (comp (ref "D4")
      (value "1N4148")
      (footprint "eagle-import:DO35-7")
      (libsource (lib "eagle-import") (part "1N4148DO35-7"))
    )
    (comp (ref "J10")
      (value "215079-4")
      (footprint "eagle-import:2150794")
      (fields (field (name "MOUSER_PART_NUMBER") "571-215079-4"))
      (libsource (lib "eagle-import") (part "215079-4"))
    )
    (comp (ref "J11")
      (value "640454-2")
      (footprint "eagle-import:HDRV2W66P0X254_1X2_762X572X100")
      (fields (field (name "MOUSER_PART_NUMBER") "571-640454-2"))
      (libsource (lib "eagle-import") (part "640454-2"))
    )
    (comp (ref "Q13")
      (value "BC337-25")
      (footprint "eagle-import:BC33725")
      (fields (field (name "MOUSER_PART_NUMBER") "637-BC337-25"))
      (libsource (lib "eagle-import") (part "BC337-25"))
    )
    (comp (ref "R19")
      (value "1.8K")
      (footprint "eagle-import:0204_7")
      (fields (field (name "PARTNO") "660-MFS1/4DCT52R47R0"))
      (libsource (lib "eagle-import") (part "R-US_0204/7"))
    )
    (comp (ref "R31")
      (value "2R5")
      (footprint "eagle-import:0204_7")
      (fields (field (name "PARTNO") "660-MFS1/4DCT52R47R0"))
      (libsource (lib "eagle-import") (part "R-US_0204/7"))
    )
  )
  (nets
    (net (code "1") (name "3V3_PERIPHERAL") (class "Default")
      (node (ref "JP1") (pin "6") (pinfunction "6_6") (pintype "passive"))
      (node (ref "JP2") (pin "1") (pinfunction "1_1") (pintype "passive"))
      (node (ref "JP4") (pin "1") (pinfunction "1_1") (pintype "passive"))
      (node (ref "Q15") (pin "2") (pinfunction "C_2") (pintype "bidirectional"))
      (node (ref "QWIIC1") (pin "2") (pinfunction "V+_2") (pintype "passive"))
      (node (ref "R12") (pin "2") (pinfunction "2_2") (pintype "passive"))
      (node (ref "R29") (pin "2") (pinfunction "2_2") (pintype "passive"))
      (node (ref "R30") (pin "2") (pinfunction "2_2") (pintype "passive"))
    )
    (net (code "2") (name "3V3_PICO") (class "Default")
      (node (ref "C10") (pin "2") (pinfunction "2_2") (pintype "passive"))
      (node (ref "C18") (pin "2") (pinfunction "2_2") (pintype "passive"))
      (node (ref "C19") (pin "2") (pinfunction "2_2") (pintype "passive"))
      (node (ref "C9") (pin "2") (pinfunction "2_2") (pintype "passive"))
      (node (ref "IC11") (pin "16") (pinfunction "VCC_16") (pintype "bidirectional"))
      (node (ref "IC12") (pin "16") (pinfunction "VCC_16") (pintype "bidirectional"))
      (node (ref "IC14") (pin "6") (pinfunction "COL_6") (pintype "passive"))
      (node (ref "IC16") (pin "16") (pinfunction "VCC_16") (pintype "bidirectional"))
      (node (ref "IC18") (pin "16") (pinfunction "VCC_16") (pintype "bidirectional"))
      (node (ref "J10") (pin "1") (pinfunction "1_1") (pintype "bidirectional"))
      (node (ref "J16") (pin "5") (pinfunction "5_5") (pintype "bidirectional"))
      (node (ref "J9") (pin "4") (pinfunction "4_4") (pintype "bidirectional"))
      (node (ref "LED2") (pin "2") (pinfunction "COMMON_A_2") (pintype "bidirectional"))
      (node (ref "Q15") (pin "1") (pinfunction "E_1") (pintype "bidirectional"))
      (node (ref "R23") (pin "1") (pinfunction "1_1") (pintype "bidirectional"))
      (node (ref "R24") (pin "1") (pinfunction "1_1") (pintype "bidirectional"))
      (node (ref "R25") (pin "1") (pinfunction "1_1") (pintype "bidirectional"))
      (node (ref "R27") (pin "1") (pinfunction "1_1") (pintype "bidirectional"))
      (node (ref "R28") (pin "2") (pinfunction "2_2") (pintype "passive"))
      (node (ref "R34") (pin "2") (pinfunction "2_2") (pintype "passive"))
    )
    (net (code "3") (name "5V") (class "Default")
      (node (ref "C15") (pin "1") (pinfunction "1_1") (pintype "passive"))
      (node (ref "C16") (pin "1") (pinfunction "1_1") (pintype "passive"))
      (node (ref "IC13") (pin "14") (pinfunction "VCC_14") (pintype "bidirectional"))
      (node (ref "IC13") (pin "2") (pinfunction "1D_2") (pintype "bidirectional"))
      (node (ref "IC13") (pin "4") (pinfunction "1~{PRE}_4") (pintype "bidirectional"))
      (node (ref "IC14") (pin "8") (pinfunction "COL_8") (pintype "passive"))
      (node (ref "IC15") (pin "2") (pinfunction "VDD_2") (pintype "power_in"))
      (node (ref "J1") (pin "2") (pinfunction "2_2") (pintype "bidirectional"))
      (node (ref "J11") (pin "1") (pinfunction "1_1") (pintype "bidirectional"))
      (node (ref "J2") (pin "6") (pinfunction "6_6") (pintype "bidirectional"))
      (node (ref "J9") (pin "2") (pinfunction "2_2") (pintype "bidirectional"))
    )
    (net (code "4") (name "12V") (class "Default")
      (node (ref "C1") (pin "2") (pinfunction "2_2") (pintype "passive"))
      (node (ref "C11") (pin "2") (pinfunction "2_2") (pintype "passive"))
      (node (ref "C12") (pin "2") (pinfunction "2_2") (pintype "passive"))
      (node (ref "C13") (pin "2") (pinfunction "2_2") (pintype "passive"))
      (node (ref "C14") (pin "2") (pinfunction "2_2") (pintype "passive"))
      (node (ref "C2") (pin "2") (pinfunction "2_2") (pintype "passive"))
      (node (ref "C3") (pin "2") (pinfunction "2_2") (pintype "passive"))
      (node (ref "C4") (pin "2") (pinfunction "2_2") (pintype "passive"))
      (node (ref "C5") (pin "2") (pinfunction "2_2") (pintype "passive"))
      (node (ref "C6") (pin "2") (pinfunction "2_2") (pintype "passive"))
      (node (ref "C7") (pin "2") (pinfunction "2_2") (pintype "passive"))
      (node (ref "C8") (pin "2") (pinfunction "2_2") (pintype "passive"))
      (node (ref "IC1") (pin "1") (pinfunction "ENA_1") (pintype "input"))
      (node (ref "IC1") (pin "6") (pinfunction "VDD_6") (pintype "power_in"))
      (node (ref "IC1") (pin "8") (pinfunction "ENB_8") (pintype "input"))
      (node (ref "IC2") (pin "1") (pinfunction "ENA_1") (pintype "input"))
      (node (ref "IC2") (pin "6") (pinfunction "VDD_6") (pintype "power_in"))
      (node (ref "IC2") (pin "8") (pinfunction "ENB_8") (pintype "input"))
      (node (ref "IC3") (pin "1") (pinfunction "ENA_1") (pintype "input"))
      (node (ref "IC3") (pin "6") (pinfunction "VDD_6") (pintype "power_in"))
      (node (ref "IC3") (pin "8") (pinfunction "ENB_8") (pintype "input"))
      (node (ref "IC4") (pin "1") (pinfunction "ENA_1") (pintype "input"))
      (node (ref "IC4") (pin "6") (pinfunction "VDD_6") (pintype "power_in"))
      (node (ref "IC4") (pin "8") (pinfunction "ENB_8") (pintype "input"))
      (node (ref "IC5") (pin "1") (pinfunction "ENA_1") (pintype "input"))
      (node (ref "IC5") (pin "6") (pinfunction "VDD_6") (pintype "power_in"))
      (node (ref "IC5") (pin "8") (pinfunction "ENB_8") (pintype "input"))
      (node (ref "IC6") (pin "1") (pinfunction "ENA_1") (pintype "input"))
      (node (ref "IC6") (pin "6") (pinfunction "VDD_6") (pintype "power_in"))
      (node (ref "IC6") (pin "8") (pinfunction "ENB_8") (pintype "input"))
      (node (ref "J2") (pin "5") (pinfunction "5_5") (pintype "bidirectional"))
    )
    (net (code "5") (name "ACCEL_INTR") (class "Default")
      (node (ref "J16") (pin "12") (pinfunction "12_12") (pintype "bidirectional"))
      (node (ref "JP2") (pin "6") (pinfunction "6_6") (pintype "passive"))
    )
    (net (code "6") (name "ADC_INTR") (class "Default")
      (node (ref "J15") (pin "15") (pinfunction "15_15") (pintype "bidirectional"))
      (node (ref "JP4") (pin "6") (pinfunction "6_6") (pintype "passive"))
    )
    (net (code "7") (name "BUTTON1") (class "Default")
      (node (ref "IC11") (pin "11") (pinfunction "A_11") (pintype "bidirectional"))
      (node (ref "J8") (pin "1") (pinfunction "1_1") (pintype "bidirectional"))
      (node (ref "R27") (pin "2") (pinfunction "2_2") (pintype "bidirectional"))
    )
    (net (code "8") (name "BUTTON2") (class "Default")
      (node (ref "IC11") (pin "12") (pinfunction "B_12") (pintype "bidirectional"))
      (node (ref "J8") (pin "2") (pinfunction "2_2") (pintype "bidirectional"))
      (node (ref "R27") (pin "3") (pinfunction "3_3") (pintype "bidirectional"))
    )
    (net (code "9") (name "BUTTON3") (class "Default")
      (node (ref "IC11") (pin "13") (pinfunction "C_13") (pintype "bidirectional"))
      (node (ref "J8") (pin "4") (pinfunction "4_4") (pintype "bidirectional"))
      (node (ref "R27") (pin "4") (pinfunction "4_4") (pintype "bidirectional"))
    )
    (net (code "10") (name "BUTTON4") (class "Default")
      (node (ref "IC11") (pin "14") (pinfunction "D_14") (pintype "bidirectional"))
      (node (ref "J8") (pin "5") (pinfunction "5_5") (pintype "bidirectional"))
      (node (ref "R27") (pin "5") (pinfunction "5_5") (pintype "bidirectional"))
    )
    (net (code "11") (name "BUTTON5") (class "Default")
      (node (ref "IC11") (pin "6") (pinfunction "H_6") (pintype "bidirectional"))
      (node (ref "J8") (pin "6") (pinfunction "6_6") (pintype "bidirectional"))
      (node (ref "R27") (pin "6") (pinfunction "6_6") (pintype "bidirectional"))
    )
    (net (code "12") (name "BUTTON6") (class "Default")
      (node (ref "IC11") (pin "5") (pinfunction "G_5") (pintype "bidirectional"))
      (node (ref "J8") (pin "7") (pinfunction "7_7") (pintype "bidirectional"))
      (node (ref "R27") (pin "7") (pinfunction "7_7") (pintype "bidirectional"))
    )
    (net (code "13") (name "BUTTON7") (class "Default")
      (node (ref "IC11") (pin "4") (pinfunction "F_4") (pintype "bidirectional"))
      (node (ref "J8") (pin "8") (pinfunction "8_8") (pintype "bidirectional"))
      (node (ref "R27") (pin "8") (pinfunction "8_8") (pintype "bidirectional"))
    )
    (net (code "14") (name "BUTTON8") (class "Default")
      (node (ref "IC11") (pin "3") (pinfunction "E_3") (pintype "bidirectional"))
      (node (ref "J8") (pin "9") (pinfunction "9_9") (pintype "bidirectional"))
      (node (ref "R27") (pin "9") (pinfunction "9_9") (pintype "bidirectional"))
    )
    (net (code "15") (name "BUTTON9") (class "Default")
      (node (ref "IC12") (pin "11") (pinfunction "A_11") (pintype "bidirectional"))
      (node (ref "J7") (pin "1") (pinfunction "1_1") (pintype "bidirectional"))
      (node (ref "R23") (pin "2") (pinfunction "2_2") (pintype "bidirectional"))
    )
    (net (code "16") (name "BUTTON10") (class "Default")
      (node (ref "IC12") (pin "12") (pinfunction "B_12") (pintype "bidirectional"))
      (node (ref "J7") (pin "2") (pinfunction "2_2") (pintype "bidirectional"))
      (node (ref "R23") (pin "3") (pinfunction "3_3") (pintype "bidirectional"))
    )
    (net (code "17") (name "BUTTON11") (class "Default")
      (node (ref "IC12") (pin "13") (pinfunction "C_13") (pintype "bidirectional"))
      (node (ref "J7") (pin "3") (pinfunction "3_3") (pintype "bidirectional"))
      (node (ref "R23") (pin "4") (pinfunction "4_4") (pintype "bidirectional"))
    )
    (net (code "18") (name "BUTTON12") (class "Default")
      (node (ref "IC12") (pin "14") (pinfunction "D_14") (pintype "bidirectional"))
      (node (ref "J7") (pin "5") (pinfunction "5_5") (pintype "bidirectional"))
      (node (ref "R23") (pin "5") (pinfunction "5_5") (pintype "bidirectional"))
    )
    (net (code "19") (name "BUTTON13") (class "Default")
      (node (ref "IC12") (pin "6") (pinfunction "H_6") (pintype "bidirectional"))
      (node (ref "J7") (pin "6") (pinfunction "6_6") (pintype "bidirectional"))
      (node (ref "R23") (pin "6") (pinfunction "6_6") (pintype "bidirectional"))
    )
    (net (code "20") (name "BUTTON14") (class "Default")
      (node (ref "IC12") (pin "5") (pinfunction "G_5") (pintype "bidirectional"))
      (node (ref "J7") (pin "7") (pinfunction "7_7") (pintype "bidirectional"))
      (node (ref "R23") (pin "7") (pinfunction "7_7") (pintype "bidirectional"))
    )
    (net (code "21") (name "BUTTON15") (class "Default")
      (node (ref "IC12") (pin "4") (pinfunction "F_4") (pintype "bidirectional"))
      (node (ref "J7") (pin "8") (pinfunction "8_8") (pintype "bidirectional"))
      (node (ref "R23") (pin "8") (pinfunction "8_8") (pintype "bidirectional"))
    )
    (net (code "22") (name "BUTTON16") (class "Default")
      (node (ref "IC12") (pin "3") (pinfunction "E_3") (pintype "bidirectional"))
      (node (ref "J7") (pin "9") (pinfunction "9_9") (pintype "bidirectional"))
      (node (ref "R23") (pin "9") (pinfunction "9_9") (pintype "bidirectional"))
    )
    (net (code "23") (name "BUTTON17") (class "Default")
      (node (ref "IC16") (pin "11") (pinfunction "A_11") (pintype "bidirectional"))
      (node (ref "J6") (pin "1") (pinfunction "1_1") (pintype "bidirectional"))
      (node (ref "R24") (pin "2") (pinfunction "2_2") (pintype "bidirectional"))
    )
    (net (code "24") (name "BUTTON18") (class "Default")
      (node (ref "IC16") (pin "12") (pinfunction "B_12") (pintype "bidirectional"))
      (node (ref "J6") (pin "2") (pinfunction "2_2") (pintype "bidirectional"))
      (node (ref "R24") (pin "3") (pinfunction "3_3") (pintype "bidirectional"))
    )
    (net (code "25") (name "BUTTON19") (class "Default")
      (node (ref "IC16") (pin "13") (pinfunction "C_13") (pintype "bidirectional"))
      (node (ref "J6") (pin "3") (pinfunction "3_3") (pintype "bidirectional"))
      (node (ref "R24") (pin "4") (pinfunction "4_4") (pintype "bidirectional"))
    )
    (net (code "26") (name "BUTTON20") (class "Default")
      (node (ref "IC16") (pin "14") (pinfunction "D_14") (pintype "bidirectional"))
      (node (ref "J6") (pin "4") (pinfunction "4_4") (pintype "bidirectional"))
      (node (ref "R24") (pin "5") (pinfunction "5_5") (pintype "bidirectional"))
    )
    (net (code "27") (name "BUTTON21") (class "Default")
      (node (ref "IC16") (pin "6") (pinfunction "H_6") (pintype "bidirectional"))
      (node (ref "J6") (pin "6") (pinfunction "6_6") (pintype "bidirectional"))
      (node (ref "R24") (pin "6") (pinfunction "6_6") (pintype "bidirectional"))
    )
    (net (code "28") (name "BUTTON22") (class "Default")
      (node (ref "IC16") (pin "5") (pinfunction "G_5") (pintype "bidirectional"))
      (node (ref "J6") (pin "7") (pinfunction "7_7") (pintype "bidirectional"))
      (node (ref "R24") (pin "7") (pinfunction "7_7") (pintype "bidirectional"))
    )
    (net (code "29") (name "BUTTON23") (class "Default")
      (node (ref "IC16") (pin "4") (pinfunction "F_4") (pintype "bidirectional"))
      (node (ref "J6") (pin "8") (pinfunction "8_8") (pintype "bidirectional"))
      (node (ref "R24") (pin "8") (pinfunction "8_8") (pintype "bidirectional"))
    )
    (net (code "30") (name "BUTTON24") (class "Default")
      (node (ref "IC16") (pin "3") (pinfunction "E_3") (pintype "bidirectional"))
      (node (ref "J6") (pin "9") (pinfunction "9_9") (pintype "bidirectional"))
      (node (ref "R24") (pin "9") (pinfunction "9_9") (pintype "bidirectional"))
    )
    (net (code "31") (name "BUTTON25") (class "Default")
      (node (ref "IC18") (pin "11") (pinfunction "A_11") (pintype "bidirectional"))
      (node (ref "J5") (pin "1") (pinfunction "1_1") (pintype "bidirectional"))
      (node (ref "R25") (pin "2") (pinfunction "2_2") (pintype "bidirectional"))
    )
    (net (code "32") (name "BUTTON26") (class "Default")
      (node (ref "IC18") (pin "12") (pinfunction "B_12") (pintype "bidirectional"))
      (node (ref "J5") (pin "2") (pinfunction "2_2") (pintype "bidirectional"))
      (node (ref "R25") (pin "3") (pinfunction "3_3") (pintype "bidirectional"))
    )
    (net (code "33") (name "BUTTON27") (class "Default")
      (node (ref "IC18") (pin "13") (pinfunction "C_13") (pintype "bidirectional"))
      (node (ref "J5") (pin "3") (pinfunction "3_3") (pintype "bidirectional"))
      (node (ref "R25") (pin "4") (pinfunction "4_4") (pintype "bidirectional"))
    )
    (net (code "34") (name "BUTTON28") (class "Default")
      (node (ref "IC18") (pin "14") (pinfunction "D_14") (pintype "bidirectional"))
      (node (ref "J5") (pin "4") (pinfunction "4_4") (pintype "bidirectional"))
      (node (ref "R25") (pin "5") (pinfunction "5_5") (pintype "bidirectional"))
    )
    (net (code "35") (name "BUTTON29") (class "Default")
      (node (ref "IC18") (pin "6") (pinfunction "H_6") (pintype "bidirectional"))
      (node (ref "J5") (pin "5") (pinfunction "5_5") (pintype "bidirectional"))
      (node (ref "R25") (pin "6") (pinfunction "6_6") (pintype "bidirectional"))
    )
    (net (code "36") (name "BUTTON30") (class "Default")
      (node (ref "IC18") (pin "5") (pinfunction "G_5") (pintype "bidirectional"))
      (node (ref "J5") (pin "7") (pinfunction "7_7") (pintype "bidirectional"))
      (node (ref "R25") (pin "7") (pinfunction "7_7") (pintype "bidirectional"))
    )
    (net (code "37") (name "BUTTON31") (class "Default")
      (node (ref "IC18") (pin "4") (pinfunction "F_4") (pintype "bidirectional"))
      (node (ref "J5") (pin "8") (pinfunction "8_8") (pintype "bidirectional"))
      (node (ref "R25") (pin "8") (pinfunction "8_8") (pintype "bidirectional"))
    )
    (net (code "38") (name "BUTTON32") (class "Default")
      (node (ref "IC18") (pin "3") (pinfunction "E_3") (pintype "bidirectional"))
      (node (ref "J5") (pin "9") (pinfunction "9_9") (pintype "bidirectional"))
      (node (ref "R25") (pin "9") (pinfunction "9_9") (pintype "bidirectional"))
    )
    (net (code "39") (name "BUTTON_CLK") (class "Default")
      (node (ref "IC11") (pin "2") (pinfunction "CLK_2") (pintype "bidirectional"))
      (node (ref "IC12") (pin "2") (pinfunction "CLK_2") (pintype "bidirectional"))
      (node (ref "IC16") (pin "2") (pinfunction "CLK_2") (pintype "bidirectional"))
      (node (ref "IC18") (pin "2") (pinfunction "CLK_2") (pintype "bidirectional"))
      (node (ref "J16") (pin "16") (pinfunction "16_16") (pintype "bidirectional"))
    )
    (net (code "40") (name "BUTTON_DATA") (class "Default")
      (node (ref "IC11") (pin "9") (pinfunction "QH_9") (pintype "bidirectional"))
      (node (ref "J16") (pin "17") (pinfunction "17_17") (pintype "bidirectional"))
    )
    (net (code "41") (name "BUTTON_SHLD") (class "Default")
      (node (ref "IC11") (pin "1") (pinfunction "SH/~{LD}_1") (pintype "bidirectional"))
      (node (ref "IC12") (pin "1") (pinfunction "SH/~{LD}_1") (pintype "bidirectional"))
      (node (ref "IC16") (pin "1") (pinfunction "SH/~{LD}_1") (pintype "bidirectional"))
      (node (ref "IC18") (pin "1") (pinfunction "SH/~{LD}_1") (pintype "bidirectional"))
      (node (ref "J16") (pin "15") (pinfunction "15_15") (pintype "bidirectional"))
    )
    (net (code "42") (name "FLASHCTL1") (class "Default")
      (node (ref "IC7") (pin "1") (pinfunction "I1_1") (pintype "input"))
      (node (ref "IC7") (pin "2") (pinfunction "I2_2") (pintype "input"))
      (node (ref "J17") (pin "20") (pinfunction "20_20") (pintype "bidirectional"))
    )
    (net (code "43") (name "FLASHCTL2") (class "Default")
      (node (ref "IC7") (pin "3") (pinfunction "I3_3") (pintype "input"))
      (node (ref "IC7") (pin "4") (pinfunction "I4_4") (pintype "input"))
      (node (ref "J17") (pin "19") (pinfunction "19_19") (pintype "bidirectional"))
    )
    (net (code "44") (name "FLASHCTL3") (class "Default")
      (node (ref "IC7") (pin "5") (pinfunction "I5_5") (pintype "input"))
      (node (ref "IC7") (pin "6") (pinfunction "I6_6") (pintype "input"))
      (node (ref "J17") (pin "17") (pinfunction "17_17") (pintype "bidirectional"))
    )
    (net (code "45") (name "FLASHCTL4") (class "Default")
      (node (ref "IC7") (pin "7") (pinfunction "I7_7") (pintype "input"))
      (node (ref "IC7") (pin "8") (pinfunction "I8_8") (pintype "input"))
      (node (ref "J17") (pin "16") (pinfunction "16_16") (pintype "bidirectional"))
    )
    (net (code "46") (name "FLASHCTL5") (class "Default")
      (node (ref "IC8") (pin "1") (pinfunction "I1_1") (pintype "input"))
      (node (ref "IC8") (pin "2") (pinfunction "I2_2") (pintype "input"))
      (node (ref "J17") (pin "15") (pinfunction "15_15") (pintype "bidirectional"))
    )
    (net (code "47") (name "FLASHCTL6") (class "Default")
      (node (ref "IC8") (pin "3") (pinfunction "I3_3") (pintype "input"))
      (node (ref "IC8") (pin "4") (pinfunction "I4_4") (pintype "input"))
      (node (ref "J17") (pin "14") (pinfunction "14_14") (pintype "bidirectional"))
    )
    (net (code "48") (name "FLASHCTL7") (class "Default")
      (node (ref "IC8") (pin "5") (pinfunction "I5_5") (pintype "input"))
      (node (ref "IC8") (pin "6") (pinfunction "I6_6") (pintype "input"))
      (node (ref "J17") (pin "12") (pinfunction "12_12") (pintype "bidirectional"))
    )
    (net (code "49") (name "FLASHCTL8") (class "Default")
      (node (ref "IC8") (pin "7") (pinfunction "I7_7") (pintype "input"))
      (node (ref "IC8") (pin "8") (pinfunction "I8_8") (pintype "input"))
      (node (ref "J17") (pin "11") (pinfunction "11_11") (pintype "bidirectional"))
    )
    (net (code "50") (name "FLASHCTL9") (class "Default")
      (node (ref "IC10") (pin "7") (pinfunction "I7_7") (pintype "input"))
      (node (ref "IC10") (pin "8") (pinfunction "I8_8") (pintype "input"))
      (node (ref "J17") (pin "10") (pinfunction "10_10") (pintype "bidirectional"))
    )
    (net (code "51") (name "FLASHCTL10") (class "Default")
      (node (ref "IC10") (pin "5") (pinfunction "I5_5") (pintype "input"))
      (node (ref "IC10") (pin "6") (pinfunction "I6_6") (pintype "input"))
      (node (ref "J17") (pin "9") (pinfunction "9_9") (pintype "bidirectional"))
    )
    (net (code "52") (name "FLASHCTL11") (class "Default")
      (node (ref "IC10") (pin "3") (pinfunction "I3_3") (pintype "input"))
      (node (ref "IC10") (pin "4") (pinfunction "I4_4") (pintype "input"))
      (node (ref "J17") (pin "7") (pinfunction "7_7") (pintype "bidirectional"))
    )
    (net (code "53") (name "FLASHCTL12") (class "Default")
      (node (ref "IC10") (pin "1") (pinfunction "I1_1") (pintype "input"))
      (node (ref "IC10") (pin "2") (pinfunction "I2_2") (pintype "input"))
      (node (ref "J17") (pin "6") (pinfunction "6_6") (pintype "bidirectional"))
    )
    (net (code "54") (name "FLASHCTL13") (class "Default")
      (node (ref "IC9") (pin "5") (pinfunction "I5_5") (pintype "input"))
      (node (ref "IC9") (pin "6") (pinfunction "I6_6") (pintype "input"))
      (node (ref "J17") (pin "5") (pinfunction "5_5") (pintype "bidirectional"))
    )
    (net (code "55") (name "FLASHCTL14") (class "Default")
      (node (ref "IC9") (pin "3") (pinfunction "I3_3") (pintype "input"))
      (node (ref "IC9") (pin "4") (pinfunction "I4_4") (pintype "input"))
      (node (ref "J17") (pin "4") (pinfunction "4_4") (pintype "bidirectional"))
    )
    (net (code "56") (name "FLASHCTL15") (class "Default")
      (node (ref "IC9") (pin "1") (pinfunction "I1_1") (pintype "input"))
      (node (ref "IC9") (pin "2") (pinfunction "I2_2") (pintype "input"))
      (node (ref "J17") (pin "2") (pinfunction "2_2") (pintype "bidirectional"))
    )
    (net (code "57") (name "FLASHCTL16") (class "Default")
      (node (ref "IC9") (pin "7") (pinfunction "I7_7") (pintype "input"))
      (node (ref "IC9") (pin "8") (pinfunction "I8_8") (pintype "input"))
      (node (ref "J17") (pin "1") (pinfunction "1_1") (pintype "bidirectional"))
    )
    (net (code "58") (name "FLASHER1") (class "Default")
      (node (ref "IC7") (pin "17") (pinfunction "O2_17") (pintype "open_collector"))
      (node (ref "IC7") (pin "18") (pinfunction "O1_18") (pintype "open_collector"))
      (node (ref "J1") (pin "15") (pinfunction "15_15") (pintype "bidirectional"))
    )
    (net (code "59") (name "FLASHER2") (class "Default")
      (node (ref "IC7") (pin "15") (pinfunction "O4_15") (pintype "open_collector"))
      (node (ref "IC7") (pin "16") (pinfunction "O3_16") (pintype "open_collector"))
      (node (ref "J1") (pin "13") (pinfunction "13_13") (pintype "bidirectional"))
    )
    (net (code "60") (name "FLASHER3") (class "Default")
      (node (ref "IC7") (pin "13") (pinfunction "O6_13") (pintype "open_collector"))
      (node (ref "IC7") (pin "14") (pinfunction "O5_14") (pintype "open_collector"))
      (node (ref "J1") (pin "11") (pinfunction "11_11") (pintype "bidirectional"))
    )
    (net (code "61") (name "FLASHER4") (class "Default")
      (node (ref "IC7") (pin "11") (pinfunction "O8_11") (pintype "open_collector"))
      (node (ref "IC7") (pin "12") (pinfunction "O7_12") (pintype "open_collector"))
      (node (ref "J1") (pin "9") (pinfunction "9_9") (pintype "bidirectional"))
    )
    (net (code "62") (name "FLASHER5") (class "Default")
      (node (ref "IC8") (pin "17") (pinfunction "O2_17") (pintype "open_collector"))
      (node (ref "IC8") (pin "18") (pinfunction "O1_18") (pintype "open_collector"))
      (node (ref "J1") (pin "7") (pinfunction "7_7") (pintype "bidirectional"))
    )
    (net (code "63") (name "FLASHER6") (class "Default")
      (node (ref "IC8") (pin "15") (pinfunction "O4_15") (pintype "open_collector"))
      (node (ref "IC8") (pin "16") (pinfunction "O3_16") (pintype "open_collector"))
      (node (ref "J1") (pin "5") (pinfunction "5_5") (pintype "bidirectional"))
    )
    (net (code "64") (name "FLASHER7") (class "Default")
      (node (ref "IC8") (pin "13") (pinfunction "O6_13") (pintype "open_collector"))
      (node (ref "IC8") (pin "14") (pinfunction "O5_14") (pintype "open_collector"))
      (node (ref "J1") (pin "3") (pinfunction "3_3") (pintype "bidirectional"))
    )
    (net (code "65") (name "FLASHER8") (class "Default")
      (node (ref "IC8") (pin "11") (pinfunction "O8_11") (pintype "open_collector"))
      (node (ref "IC8") (pin "12") (pinfunction "O7_12") (pintype "open_collector"))
      (node (ref "J1") (pin "1") (pinfunction "1_1") (pintype "bidirectional"))
    )
    (net (code "66") (name "FLASHER9") (class "Default")
      (node (ref "IC10") (pin "11") (pinfunction "O8_11") (pintype "open_collector"))
      (node (ref "IC10") (pin "12") (pinfunction "O7_12") (pintype "open_collector"))
      (node (ref "J1") (pin "16") (pinfunction "16_16") (pintype "bidirectional"))
    )
    (net (code "67") (name "FLASHER10") (class "Default")
      (node (ref "IC10") (pin "13") (pinfunction "O6_13") (pintype "open_collector"))
      (node (ref "IC10") (pin "14") (pinfunction "O5_14") (pintype "open_collector"))
      (node (ref "J1") (pin "14") (pinfunction "14_14") (pintype "bidirectional"))
    )
    (net (code "68") (name "FLASHER11") (class "Default")
      (node (ref "IC10") (pin "15") (pinfunction "O4_15") (pintype "open_collector"))
      (node (ref "IC10") (pin "16") (pinfunction "O3_16") (pintype "open_collector"))
      (node (ref "J1") (pin "12") (pinfunction "12_12") (pintype "bidirectional"))
    )
    (net (code "69") (name "FLASHER12") (class "Default")
      (node (ref "IC10") (pin "17") (pinfunction "O2_17") (pintype "open_collector"))
      (node (ref "IC10") (pin "18") (pinfunction "O1_18") (pintype "open_collector"))
      (node (ref "J1") (pin "10") (pinfunction "10_10") (pintype "bidirectional"))
    )
    (net (code "70") (name "FLASHER13") (class "Default")
      (node (ref "IC9") (pin "13") (pinfunction "O6_13") (pintype "open_collector"))
      (node (ref "IC9") (pin "14") (pinfunction "O5_14") (pintype "open_collector"))
      (node (ref "J1") (pin "8") (pinfunction "8_8") (pintype "bidirectional"))
    )
    (net (code "71") (name "FLASHER14") (class "Default")
      (node (ref "IC9") (pin "15") (pinfunction "O4_15") (pintype "open_collector"))
      (node (ref "IC9") (pin "16") (pinfunction "O3_16") (pintype "open_collector"))
      (node (ref "J1") (pin "6") (pinfunction "6_6") (pintype "bidirectional"))
    )
    (net (code "72") (name "FLASHER15") (class "Default")
      (node (ref "IC9") (pin "17") (pinfunction "O2_17") (pintype "open_collector"))
      (node (ref "IC9") (pin "18") (pinfunction "O1_18") (pintype "open_collector"))
      (node (ref "J1") (pin "4") (pinfunction "4_4") (pintype "bidirectional"))
    )
    (net (code "73") (name "FLASHER16") (class "Default")
      (node (ref "IC9") (pin "11") (pinfunction "O8_11") (pintype "open_collector"))
      (node (ref "IC9") (pin "12") (pinfunction "O7_12") (pintype "open_collector"))
      (node (ref "J13") (pin "1") (pinfunction "1_1") (pintype "bidirectional"))
    )
    (net (code "74") (name "GND") (class "Default")
      (node (ref "C1") (pin "1") (pinfunction "1_1") (pintype "passive"))
      (node (ref "C10") (pin "1") (pinfunction "1_1") (pintype "passive"))
      (node (ref "C11") (pin "1") (pinfunction "1_1") (pintype "passive"))
      (node (ref "C12") (pin "1") (pinfunction "1_1") (pintype "passive"))
      (node (ref "C13") (pin "1") (pinfunction "1_1") (pintype "passive"))
      (node (ref "C14") (pin "1") (pinfunction "1_1") (pintype "passive"))
      (node (ref "C15") (pin "2") (pinfunction "2_2") (pintype "passive"))
      (node (ref "C16") (pin "2") (pinfunction "2_2") (pintype "passive"))
      (node (ref "C18") (pin "1") (pinfunction "1_1") (pintype "passive"))
      (node (ref "C19") (pin "1") (pinfunction "1_1") (pintype "passive"))
      (node (ref "C2") (pin "1") (pinfunction "1_1") (pintype "passive"))
      (node (ref "C3") (pin "1") (pinfunction "1_1") (pintype "passive"))
      (node (ref "C4") (pin "1") (pinfunction "1_1") (pintype "passive"))
      (node (ref "C5") (pin "1") (pinfunction "1_1") (pintype "passive"))
      (node (ref "C6") (pin "1") (pinfunction "1_1") (pintype "passive"))
      (node (ref "C7") (pin "1") (pinfunction "1_1") (pintype "passive"))
      (node (ref "C8") (pin "1") (pinfunction "1_1") (pintype "passive"))
      (node (ref "C9") (pin "1") (pinfunction "1_1") (pintype "passive"))
      (node (ref "D4") (pin "C") (pinfunction "C_C") (pintype "passive"))
      (node (ref "IC1") (pin "3") (pinfunction "GND_3") (pintype "power_in"))
      (node (ref "IC10") (pin "9") (pinfunction "GND_9") (pintype "power_in"))
      (node (ref "IC11") (pin "15") (pinfunction "CLK_INH_15") (pintype "bidirectional"))
      (node (ref "IC11") (pin "8") (pinfunction "GND_8") (pintype "bidirectional"))
      (node (ref "IC12") (pin "15") (pinfunction "CLK_INH_15") (pintype "bidirectional"))
      (node (ref "IC12") (pin "8") (pinfunction "GND_8") (pintype "bidirectional"))
      (node (ref "IC13") (pin "7") (pinfunction "GND_7") (pintype "bidirectional"))
      (node (ref "IC15") (pin "3") (pinfunction "GND_3") (pintype "power_in"))
      (node (ref "IC16") (pin "15") (pinfunction "CLK_INH_15") (pintype "bidirectional"))
      (node (ref "IC16") (pin "8") (pinfunction "GND_8") (pintype "bidirectional"))
      (node (ref "IC18") (pin "15") (pinfunction "CLK_INH_15") (pintype "bidirectional"))
      (node (ref "IC18") (pin "8") (pinfunction "GND_8") (pintype "bidirectional"))
      (node (ref "IC2") (pin "3") (pinfunction "GND_3") (pintype "power_in"))
      (node (ref "IC3") (pin "3") (pinfunction "GND_3") (pintype "power_in"))
      (node (ref "IC4") (pin "3") (pinfunction "GND_3") (pintype "power_in"))
      (node (ref "IC5") (pin "3") (pinfunction "GND_3") (pintype "power_in"))
      (node (ref "IC6") (pin "3") (pinfunction "GND_3") (pintype "power_in"))
      (node (ref "IC7") (pin "9") (pinfunction "GND_9") (pintype "power_in"))
      (node (ref "IC8") (pin "9") (pinfunction "GND_9") (pintype "power_in"))
      (node (ref "IC9") (pin "9") (pinfunction "GND_9") (pintype "power_in"))
      (node (ref "J10") (pin "2") (pinfunction "2_2") (pintype "bidirectional"))
      (node (ref "J10") (pin "4") (pinfunction "4_4") (pintype "bidirectional"))
      (node (ref "J12") (pin "2") (pinfunction "2_2") (pintype "passive"))
      (node (ref "J13") (pin "2") (pinfunction "2_2") (pintype "bidirectional"))
      (node (ref "J14") (pin "2") (pinfunction "2_2") (pintype "bidirectional"))
      (node (ref "J14") (pin "4") (pinfunction "4_4") (pintype "bidirectional"))
      (node (ref "J14") (pin "6") (pinfunction "6_6") (pintype "bidirectional"))
      (node (ref "J14") (pin "8") (pinfunction "8_8") (pintype "bidirectional"))
      (node (ref "J15") (pin "13") (pinfunction "13_13") (pintype "bidirectional"))
      (node (ref "J15") (pin "18") (pinfunction "18_18") (pintype "bidirectional"))
      (node (ref "J15") (pin "3") (pinfunction "3_3") (pintype "bidirectional"))
      (node (ref "J15") (pin "8") (pinfunction "8_8") (pintype "bidirectional"))
      (node (ref "J16") (pin "13") (pinfunction "13_13") (pintype "bidirectional"))
      (node (ref "J16") (pin "18") (pinfunction "18_18") (pintype "bidirectional"))
      (node (ref "J16") (pin "3") (pinfunction "3_3") (pintype "bidirectional"))
      (node (ref "J16") (pin "8") (pinfunction "8_8") (pintype "bidirectional"))
      (node (ref "J17") (pin "13") (pinfunction "13_13") (pintype "bidirectional"))
      (node (ref "J17") (pin "18") (pinfunction "18_18") (pintype "bidirectional"))
      (node (ref "J17") (pin "3") (pinfunction "3_3") (pintype "bidirectional"))
      (node (ref "J17") (pin "8") (pinfunction "8_8") (pintype "bidirectional"))
      (node (ref "J18") (pin "13") (pinfunction "13_13") (pintype "bidirectional"))
      (node (ref "J18") (pin "18") (pinfunction "18_18") (pintype "bidirectional"))
      (node (ref "J18") (pin "3") (pinfunction "3_3") (pintype "bidirectional"))
      (node (ref "J18") (pin "8") (pinfunction "8_8") (pintype "bidirectional"))
      (node (ref "J2") (pin "1") (pinfunction "1_1") (pintype "bidirectional"))
      (node (ref "J2") (pin "2") (pinfunction "2_2") (pintype "bidirectional"))
      (node (ref "J2") (pin "3") (pinfunction "3_3") (pintype "bidirectional"))
      (node (ref "J2") (pin "4") (pinfunction "4_4") (pintype "bidirectional"))
      (node (ref "J5") (pin "10") (pinfunction "10_10") (pintype "bidirectional"))
      (node (ref "J6") (pin "10") (pinfunction "10_10") (pintype "bidirectional"))
      (node (ref "J7") (pin "10") (pinfunction "10_10") (pintype "bidirectional"))
      (node (ref "J8") (pin "10") (pinfunction "10_10") (pintype "bidirectional"))
      (node (ref "J9") (pin "3") (pinfunction "3_3") (pintype "bidirectional"))
      (node (ref "JP2") (pin "3") (pinfunction "3_3") (pintype "passive"))
      (node (ref "JP4") (pin "2") (pinfunction "2_2") (pintype "passive"))
      (node (ref "JP4") (pin "5") (pinfunction "5_5") (pintype "passive"))
      (node (ref "Q1") (pin "3") (pinfunction "S_3") (pintype "passive"))
      (node (ref "Q10") (pin "3") (pinfunction "S_3") (pintype "passive"))
      (node (ref "Q11") (pin "3") (pinfunction "S_3") (pintype "passive"))
      (node (ref "Q12") (pin "3") (pinfunction "S_3") (pintype "passive"))
      (node (ref "Q16") (pin "1") (pinfunction "E_1") (pintype "bidirectional"))
      (node (ref "Q2") (pin "3") (pinfunction "S_3") (pintype "passive"))
      (node (ref "Q3") (pin "3") (pinfunction "S_3") (pintype "passive"))
      (node (ref "Q4") (pin "3") (pinfunction "S_3") (pintype "passive"))
      (node (ref "Q5") (pin "3") (pinfunction "S_3") (pintype "passive"))
      (node (ref "Q6") (pin "3") (pinfunction "S_3") (pintype "passive"))
      (node (ref "Q7") (pin "3") (pinfunction "S_3") (pintype "passive"))
      (node (ref "Q8") (pin "3") (pinfunction "S_3") (pintype "passive"))
      (node (ref "Q9") (pin "3") (pinfunction "S_3") (pintype "passive"))
      (node (ref "QWIIC1") (pin "1") (pinfunction "GND_1") (pintype "passive"))
      (node (ref "QWIIC1") (pin "MT1") (pinfunction "MT_MT1") (pintype "bidirectional"))
      (node (ref "QWIIC1") (pin "MT2") (pinfunction "MT_MT2") (pintype "bidirectional"))
      (node (ref "R13") (pin "1") (pinfunction "1_1") (pintype "passive"))
      (node (ref "R18") (pin "1") (pinfunction "1_1") (pintype "passive"))
      (node (ref "R20") (pin "2") (pinfunction "2_2") (pintype "passive"))
      (node (ref "R21") (pin "1") (pinfunction "1_1") (pintype "passive"))
      (node (ref "R22") (pin "1") (pinfunction "1_1") (pintype "passive"))
      (node (ref "R31") (pin "1") (pinfunction "1_1") (pintype "passive"))
      (node (ref "S1") (pin "1") (pinfunction "S_1") (pintype "passive"))
      (node (ref "S1") (pin "2") (pinfunction "S1_2") (pintype "passive"))
      (node (ref "S2") (pin "1") (pinfunction "S_1") (pintype "passive"))
      (node (ref "S2") (pin "2") (pinfunction "S1_2") (pintype "passive"))
    )
    (net (code "75") (name "IR_IN") (class "Default")
      (node (ref "J10") (pin "3") (pinfunction "3_3") (pintype "bidirectional"))
      (node (ref "J15") (pin "6") (pinfunction "6_6") (pintype "bidirectional"))
    )
    (net (code "76") (name "IR_LED_CATHODE") (class "Default")
      (node (ref "J11") (pin "2") (pinfunction "2_2") (pintype "bidirectional"))
      (node (ref "Q13") (pin "1") (pinfunction "C_1") (pintype "bidirectional"))
    )
    (net (code "77") (name "IR_OUT") (class "Default")
      (node (ref "J15") (pin "1") (pinfunction "1_1") (pintype "bidirectional"))
      (node (ref "R19") (pin "1") (pinfunction "1_1") (pintype "passive"))
    )
    (net (code "78") (name "LED_B") (class "Default")
      (node (ref "J15") (pin "4") (pinfunction "4_4") (pintype "bidirectional"))
      (node (ref "R10") (pin "1") (pinfunction "1_1") (pintype "passive"))
    )
    (net (code "79") (name "LED_G") (class "Default")
      (node (ref "J15") (pin "2") (pinfunction "2_2") (pintype "bidirectional"))
      (node (ref "R11") (pin "1") (pinfunction "1_1") (pintype "passive"))
    )
    (net (code "80") (name "LED_R") (class "Default")
      (node (ref "J15") (pin "5") (pinfunction "5_5") (pintype "bidirectional"))
      (node (ref "R9") (pin "1") (pinfunction "1_1") (pintype "passive"))
    )
    (net (code "81") (name "Net-(D1-K)") (class "Default")
      (node (ref "D1") (pin "1") (pinfunction "K_1") (pintype "bidirectional"))
      (node (ref "J18") (pin "2") (pinfunction "2_2") (pintype "bidirectional"))
    )
    (net (code "82") (name "Net-(D3-PadC)") (class "Default")
      (node (ref "D3") (pin "C") (pinfunction "C_C") (pintype "passive"))
      (node (ref "D4") (pin "A") (pinfunction "A_A") (pintype "passive"))
    )
    (net (code "83") (name "Net-(IC1-OUTA)") (class "Default")
      (node (ref "IC1") (pin "7") (pinfunction "OUTA_7") (pintype "output"))
      (node (ref "R1") (pin "1") (pinfunction "1_1") (pintype "passive"))
    )
    (net (code "84") (name "Net-(IC1-OUTB)") (class "Default")
      (node (ref "IC1") (pin "5") (pinfunction "OUTB_5") (pintype "output"))
      (node (ref "R2") (pin "1") (pinfunction "1_1") (pintype "passive"))
    )
    (net (code "85") (name "Net-(IC2-OUTA)") (class "Default")
      (node (ref "IC2") (pin "7") (pinfunction "OUTA_7") (pintype "output"))
      (node (ref "R3") (pin "1") (pinfunction "1_1") (pintype "passive"))
    )
    (net (code "86") (name "Net-(IC2-OUTB)") (class "Default")
      (node (ref "IC2") (pin "5") (pinfunction "OUTB_5") (pintype "output"))
      (node (ref "R4") (pin "1") (pinfunction "1_1") (pintype "passive"))
    )
    (net (code "87") (name "Net-(IC3-OUTA)") (class "Default")
      (node (ref "IC3") (pin "7") (pinfunction "OUTA_7") (pintype "output"))
      (node (ref "R5") (pin "1") (pinfunction "1_1") (pintype "passive"))
    )
    (net (code "88") (name "Net-(IC3-OUTB)") (class "Default")
      (node (ref "IC3") (pin "5") (pinfunction "OUTB_5") (pintype "output"))
      (node (ref "R6") (pin "1") (pinfunction "1_1") (pintype "passive"))
    )
    (net (code "89") (name "Net-(IC4-OUTA)") (class "Default")
      (node (ref "IC4") (pin "7") (pinfunction "OUTA_7") (pintype "output"))
      (node (ref "R7") (pin "1") (pinfunction "1_1") (pintype "passive"))
    )
    (net (code "90") (name "Net-(IC4-OUTB)") (class "Default")
      (node (ref "IC4") (pin "5") (pinfunction "OUTB_5") (pintype "output"))
      (node (ref "R8") (pin "1") (pinfunction "1_1") (pintype "passive"))
    )
    (net (code "91") (name "Net-(IC5-OUTA)") (class "Default")
      (node (ref "IC5") (pin "7") (pinfunction "OUTA_7") (pintype "output"))
      (node (ref "R14") (pin "1") (pinfunction "1_1") (pintype "passive"))
    )
    (net (code "92") (name "Net-(IC5-OUTB)") (class "Default")
      (node (ref "IC5") (pin "5") (pinfunction "OUTB_5") (pintype "output"))
      (node (ref "R15") (pin "1") (pinfunction "1_1") (pintype "passive"))
    )
    (net (code "93") (name "Net-(IC6-OUTA)") (class "Default")
      (node (ref "IC6") (pin "7") (pinfunction "OUTA_7") (pintype "output"))
      (node (ref "R16") (pin "1") (pinfunction "1_1") (pintype "passive"))
    )
    (net (code "94") (name "Net-(IC6-OUTB)") (class "Default")
      (node (ref "IC6") (pin "5") (pinfunction "OUTB_5") (pintype "output"))
      (node (ref "R17") (pin "1") (pinfunction "1_1") (pintype "passive"))
    )
    (net (code "95") (name "Net-(IC11-SER)") (class "Default")
      (node (ref "IC11") (pin "10") (pinfunction "SER_10") (pintype "bidirectional"))
      (node (ref "IC12") (pin "9") (pinfunction "QH_9") (pintype "bidirectional"))
    )
    (net (code "96") (name "Net-(IC12-SER)") (class "Default")
      (node (ref "IC12") (pin "10") (pinfunction "SER_10") (pintype "bidirectional"))
      (node (ref "IC16") (pin "9") (pinfunction "QH_9") (pintype "bidirectional"))
    )
    (net (code "97") (name "Net-(IC13-1CLK)") (class "Default")
      (node (ref "IC13") (pin "3") (pinfunction "1CLK_3") (pintype "bidirectional"))
      (node (ref "IC14") (pin "7") (pinfunction "EMIT_7") (pintype "passive"))
      (node (ref "R20") (pin "1") (pinfunction "1_1") (pintype "passive"))
    )
    (net (code "98") (name "Net-(IC13-1Q)") (class "Default")
      (node (ref "IC13") (pin "5") (pinfunction "1Q_5") (pintype "bidirectional"))
      (node (ref "IC14") (pin "3") (pinfunction "A_3") (pintype "passive"))
    )
    (net (code "99") (name "Net-(IC13-~{1CLR})") (class "Default")
      (node (ref "IC13") (pin "1") (pinfunction "~{1CLR}_1") (pintype "bidirectional"))
      (node (ref "IC15") (pin "1") (pinfunction "OUT_1") (pintype "output"))
    )
    (net (code "100") (name "Net-(IC14A-C)") (class "Default")
      (node (ref "IC14") (pin "2") (pinfunction "C_2") (pintype "passive"))
      (node (ref "R18") (pin "2") (pinfunction "2_2") (pintype "passive"))
    )
    (net (code "101") (name "Net-(IC14B-C)") (class "Default")
      (node (ref "IC14") (pin "4") (pinfunction "C_4") (pintype "passive"))
      (node (ref "R21") (pin "2") (pinfunction "2_2") (pintype "passive"))
    )
    (net (code "102") (name "Net-(IC16-SER)") (class "Default")
      (node (ref "IC16") (pin "10") (pinfunction "SER_10") (pintype "bidirectional"))
      (node (ref "IC18") (pin "9") (pinfunction "QH_9") (pintype "bidirectional"))
    )
    (net (code "103") (name "Net-(J18-Pad5)") (class "Default")
      (node (ref "J18") (pin "5") (pinfunction "5_5") (pintype "bidirectional"))
      (node (ref "R32") (pin "2") (pinfunction "2_2") (pintype "passive"))
    )
    (net (code "104") (name "Net-(JP3-Pad2)") (class "Default")
      (node (ref "JP3") (pin "2") (pinfunction "2_2") (pintype "passive"))
      (node (ref "R12") (pin "1") (pinfunction "1_1") (pintype "passive"))
      (node (ref "R13") (pin "2") (pinfunction "2_2") (pintype "passive"))
    )
    (net (code "105") (name "Net-(LED2-BLUE_K)") (class "Default")
      (node (ref "LED2") (pin "3") (pinfunction "BLUE_K_3") (pintype "bidirectional"))
      (node (ref "R10") (pin "2") (pinfunction "2_2") (pintype "passive"))
    )
    (net (code "106") (name "Net-(LED2-GREEN_K)") (class "Default")
      (node (ref "LED2") (pin "4") (pinfunction "GREEN_K_4") (pintype "bidirectional"))
      (node (ref "R11") (pin "2") (pinfunction "2_2") (pintype "passive"))
    )
    (net (code "107") (name "Net-(LED2-RED_K)") (class "Default")
      (node (ref "LED2") (pin "1") (pinfunction "RED_K_1") (pintype "bidirectional"))
      (node (ref "R9") (pin "2") (pinfunction "2_2") (pintype "passive"))
    )
    (net (code "108") (name "Net-(Q1-G)") (class "Default")
      (node (ref "Q1") (pin "1") (pinfunction "G_1") (pintype "passive"))
      (node (ref "R1") (pin "2") (pinfunction "2_2") (pintype "passive"))
    )
    (net (code "109") (name "Net-(Q2-G)") (class "Default")
      (node (ref "Q2") (pin "1") (pinfunction "G_1") (pintype "passive"))
      (node (ref "R2") (pin "2") (pinfunction "2_2") (pintype "passive"))
    )
    (net (code "110") (name "Net-(Q3-G)") (class "Default")
      (node (ref "Q3") (pin "1") (pinfunction "G_1") (pintype "passive"))
      (node (ref "R3") (pin "2") (pinfunction "2_2") (pintype "passive"))
    )
    (net (code "111") (name "Net-(Q4-G)") (class "Default")
      (node (ref "Q4") (pin "1") (pinfunction "G_1") (pintype "passive"))
      (node (ref "R4") (pin "2") (pinfunction "2_2") (pintype "passive"))
    )
    (net (code "112") (name "Net-(Q5-G)") (class "Default")
      (node (ref "Q5") (pin "1") (pinfunction "G_1") (pintype "passive"))
      (node (ref "R5") (pin "2") (pinfunction "2_2") (pintype "passive"))
    )
    (net (code "113") (name "Net-(Q6-G)") (class "Default")
      (node (ref "Q6") (pin "1") (pinfunction "G_1") (pintype "passive"))
      (node (ref "R6") (pin "2") (pinfunction "2_2") (pintype "passive"))
    )
    (net (code "114") (name "Net-(Q7-G)") (class "Default")
      (node (ref "Q7") (pin "1") (pinfunction "G_1") (pintype "passive"))
      (node (ref "R7") (pin "2") (pinfunction "2_2") (pintype "passive"))
    )
    (net (code "115") (name "Net-(Q8-G)") (class "Default")
      (node (ref "Q8") (pin "1") (pinfunction "G_1") (pintype "passive"))
      (node (ref "R8") (pin "2") (pinfunction "2_2") (pintype "passive"))
    )
    (net (code "116") (name "Net-(Q9-G)") (class "Default")
      (node (ref "Q9") (pin "1") (pinfunction "G_1") (pintype "passive"))
      (node (ref "R14") (pin "2") (pinfunction "2_2") (pintype "passive"))
    )
    (net (code "117") (name "Net-(Q10-G)") (class "Default")
      (node (ref "Q10") (pin "1") (pinfunction "G_1") (pintype "passive"))
      (node (ref "R15") (pin "2") (pinfunction "2_2") (pintype "passive"))
    )
    (net (code "118") (name "Net-(Q11-G)") (class "Default")
      (node (ref "Q11") (pin "1") (pinfunction "G_1") (pintype "passive"))
      (node (ref "R16") (pin "2") (pinfunction "2_2") (pintype "passive"))
    )
    (net (code "119") (name "Net-(Q12-G)") (class "Default")
      (node (ref "Q12") (pin "1") (pinfunction "G_1") (pintype "passive"))
      (node (ref "R17") (pin "2") (pinfunction "2_2") (pintype "passive"))
    )
    (net (code "120") (name "Net-(Q13-B)") (class "Default")
      (node (ref "D3") (pin "A") (pinfunction "A_A") (pintype "passive"))
      (node (ref "Q13") (pin "2") (pinfunction "B_2") (pintype "bidirectional"))
      (node (ref "R19") (pin "2") (pinfunction "2_2") (pintype "passive"))
    )
    (net (code "121") (name "Net-(Q13-E)") (class "Default")
      (node (ref "Q13") (pin "3") (pinfunction "E_3") (pintype "bidirectional"))
      (node (ref "R31") (pin "2") (pinfunction "2_2") (pintype "passive"))
    )
    (net (code "122") (name "Net-(Q15-B)") (class "Default")
      (node (ref "Q15") (pin "3") (pinfunction "B_3") (pintype "bidirectional"))
      (node (ref "R26") (pin "2") (pinfunction "2_2") (pintype "passive"))
    )
    (net (code "123") (name "Net-(Q16-B)") (class "Default")
      (node (ref "Q16") (pin "2") (pinfunction "B_2") (pintype "bidirectional"))
      (node (ref "R33") (pin "2") (pinfunction "2_2") (pintype "passive"))
    )
    (net (code "124") (name "Net-(Q16-C)") (class "Default")
      (node (ref "J18") (pin "11") (pinfunction "11_11") (pintype "bidirectional"))
      (node (ref "Q16") (pin "3") (pinfunction "C_3") (pintype "bidirectional"))
      (node (ref "R32") (pin "1") (pinfunction "1_1") (pintype "passive"))
      (node (ref "S2") (pin "3") (pinfunction "P_3") (pintype "passive"))
      (node (ref "S2") (pin "4") (pinfunction "P1_4") (pintype "passive"))
    )
    (net (code "125") (name "Net-(S1-P)") (class "Default")
      (node (ref "J16") (pin "11") (pinfunction "11_11") (pintype "bidirectional"))
      (node (ref "R34") (pin "1") (pinfunction "1_1") (pintype "passive"))
      (node (ref "S1") (pin "3") (pinfunction "P_3") (pintype "passive"))
      (node (ref "S1") (pin "4") (pinfunction "P1_4") (pintype "passive"))
    )
    (net (code "126") (name "OUT1") (class "Default")
      (node (ref "J4") (pin "1") (pinfunction "1_1") (pintype "bidirectional"))
      (node (ref "Q1") (pin "2") (pinfunction "D_2") (pintype "passive"))
    )
    (net (code "127") (name "OUT2") (class "Default")
      (node (ref "J4") (pin "3") (pinfunction "3_3") (pintype "bidirectional"))
      (node (ref "Q2") (pin "2") (pinfunction "D_2") (pintype "passive"))
    )
    (net (code "128") (name "OUT3") (class "Default")
      (node (ref "J4") (pin "4") (pinfunction "4_4") (pintype "bidirectional"))
      (node (ref "Q3") (pin "2") (pinfunction "D_2") (pintype "passive"))
    )
    (net (code "129") (name "OUT4") (class "Default")
      (node (ref "J4") (pin "5") (pinfunction "5_5") (pintype "bidirectional"))
      (node (ref "Q4") (pin "2") (pinfunction "D_2") (pintype "passive"))
    )
    (net (code "130") (name "OUT5") (class "Default")
      (node (ref "J4") (pin "6") (pinfunction "6_6") (pintype "bidirectional"))
      (node (ref "Q5") (pin "2") (pinfunction "D_2") (pintype "passive"))
    )
    (net (code "131") (name "OUT6") (class "Default")
      (node (ref "J4") (pin "7") (pinfunction "7_7") (pintype "bidirectional"))
      (node (ref "Q6") (pin "2") (pinfunction "D_2") (pintype "passive"))
    )
    (net (code "132") (name "OUT7") (class "Default")
      (node (ref "J4") (pin "8") (pinfunction "8_8") (pintype "bidirectional"))
      (node (ref "Q7") (pin "2") (pinfunction "D_2") (pintype "passive"))
    )
    (net (code "133") (name "OUT8") (class "Default")
      (node (ref "J4") (pin "9") (pinfunction "9_9") (pintype "bidirectional"))
      (node (ref "Q8") (pin "2") (pinfunction "D_2") (pintype "passive"))
    )
    (net (code "134") (name "OUT9") (class "Default")
      (node (ref "J3") (pin "1") (pinfunction "1_1") (pintype "bidirectional"))
      (node (ref "Q9") (pin "2") (pinfunction "D_2") (pintype "passive"))
    )
    (net (code "135") (name "OUT10") (class "Default")
      (node (ref "J3") (pin "3") (pinfunction "3_3") (pintype "bidirectional"))
      (node (ref "Q10") (pin "2") (pinfunction "D_2") (pintype "passive"))
    )
    (net (code "136") (name "OUT11") (class "Default")
      (node (ref "J3") (pin "4") (pinfunction "4_4") (pintype "bidirectional"))
      (node (ref "Q11") (pin "2") (pinfunction "D_2") (pintype "passive"))
    )
    (net (code "137") (name "OUT12") (class "Default")
      (node (ref "J3") (pin "5") (pinfunction "5_5") (pintype "bidirectional"))
      (node (ref "Q12") (pin "2") (pinfunction "D_2") (pintype "passive"))
    )
    (net (code "138") (name "OUTCTL1") (class "Default")
      (node (ref "IC1") (pin "2") (pinfunction "INA_2") (pintype "input"))
      (node (ref "J15") (pin "11") (pinfunction "11_11") (pintype "bidirectional"))
    )
    (net (code "139") (name "OUTCTL2") (class "Default")
      (node (ref "IC1") (pin "4") (pinfunction "INB_4") (pintype "input"))
      (node (ref "J15") (pin "12") (pinfunction "12_12") (pintype "bidirectional"))
    )
    (net (code "140") (name "OUTCTL3") (class "Default")
      (node (ref "IC2") (pin "2") (pinfunction "INA_2") (pintype "input"))
      (node (ref "J15") (pin "19") (pinfunction "19_19") (pintype "bidirectional"))
    )
    (net (code "141") (name "OUTCTL4") (class "Default")
      (node (ref "IC2") (pin "4") (pinfunction "INB_4") (pintype "input"))
      (node (ref "J15") (pin "20") (pinfunction "20_20") (pintype "bidirectional"))
    )
    (net (code "142") (name "OUTCTL5") (class "Default")
      (node (ref "IC3") (pin "2") (pinfunction "INA_2") (pintype "input"))
      (node (ref "J18") (pin "20") (pinfunction "20_20") (pintype "bidirectional"))
    )
    (net (code "143") (name "OUTCTL6") (class "Default")
      (node (ref "IC3") (pin "4") (pinfunction "INB_4") (pintype "input"))
      (node (ref "J18") (pin "19") (pinfunction "19_19") (pintype "bidirectional"))
    )
    (net (code "144") (name "OUTCTL7") (class "Default")
      (node (ref "IC4") (pin "2") (pinfunction "INA_2") (pintype "input"))
      (node (ref "J18") (pin "17") (pinfunction "17_17") (pintype "bidirectional"))
    )
    (net (code "145") (name "OUTCTL8") (class "Default")
      (node (ref "IC4") (pin "4") (pinfunction "INB_4") (pintype "input"))
      (node (ref "J18") (pin "16") (pinfunction "16_16") (pintype "bidirectional"))
    )
    (net (code "146") (name "OUTCTL9") (class "Default")
      (node (ref "IC5") (pin "2") (pinfunction "INA_2") (pintype "input"))
      (node (ref "J18") (pin "12") (pinfunction "12_12") (pintype "bidirectional"))
    )
    (net (code "147") (name "OUTCTL10") (class "Default")
      (node (ref "IC5") (pin "4") (pinfunction "INB_4") (pintype "input"))
      (node (ref "J18") (pin "14") (pinfunction "14_14") (pintype "bidirectional"))
    )
    (net (code "148") (name "OUTCTL11") (class "Default")
      (node (ref "IC6") (pin "2") (pinfunction "INA_2") (pintype "input"))
      (node (ref "J18") (pin "15") (pinfunction "15_15") (pintype "bidirectional"))
    )
    (net (code "149") (name "OUTCTL12") (class "Default")
      (node (ref "IC6") (pin "4") (pinfunction "INB_4") (pintype "input"))
      (node (ref "J18") (pin "7") (pinfunction "7_7") (pintype "bidirectional"))
    )
    (net (code "150") (name "PLUNGER_ADC") (class "Default")
      (node (ref "J16") (pin "7") (pinfunction "7_7") (pintype "bidirectional"))
      (node (ref "J9") (pin "8") (pinfunction "8_8") (pintype "bidirectional"))
      (node (ref "JP3") (pin "5") (pinfunction "5_5") (pintype "passive"))
    )
    (net (code "151") (name "PLUNGER_IRQ1_SCL") (class "Default")
      (node (ref "J15") (pin "17") (pinfunction "17_17") (pintype "bidirectional"))
      (node (ref "J9") (pin "6") (pinfunction "6_6") (pintype "bidirectional"))
    )
    (net (code "152") (name "PLUNGER_IRQ2") (class "Default")
      (node (ref "J15") (pin "14") (pinfunction "14_14") (pintype "bidirectional"))
      (node (ref "J9") (pin "5") (pinfunction "5_5") (pintype "bidirectional"))
    )
    (net (code "153") (name "PLUNGER_SDA") (class "Default")
      (node (ref "J15") (pin "16") (pinfunction "16_16") (pintype "bidirectional"))
      (node (ref "J9") (pin "1") (pinfunction "1_1") (pintype "bidirectional"))
    )
    (net (code "154") (name "PSU2_STATUS_SENSE") (class "Default")
      (node (ref "IC14") (pin "5") (pinfunction "EMIT_5") (pintype "passive"))
      (node (ref "J16") (pin "10") (pinfunction "10_10") (pintype "bidirectional"))
      (node (ref "R22") (pin "2") (pinfunction "2_2") (pintype "passive"))
    )
    (net (code "155") (name "PSU2_STATUS_SET") (class "Default")
      (node (ref "IC14") (pin "1") (pinfunction "A_1") (pintype "passive"))
      (node (ref "J16") (pin "9") (pinfunction "9_9") (pintype "bidirectional"))
    )
    (net (code "156") (name "SCL") (class "Default")
      (node (ref "J14") (pin "3") (pinfunction "3_3") (pintype "bidirectional"))
      (node (ref "J15") (pin "10") (pinfunction "10_10") (pintype "bidirectional"))
      (node (ref "J18") (pin "9") (pinfunction "9_9") (pintype "bidirectional"))
      (node (ref "JP2") (pin "4") (pinfunction "4_4") (pintype "passive"))
      (node (ref "JP4") (pin "3") (pinfunction "3_3") (pintype "passive"))
      (node (ref "QWIIC1") (pin "4") (pinfunction "SCL_4") (pintype "passive"))
      (node (ref "R30") (pin "1") (pinfunction "1_1") (pintype "passive"))
    )
    (net (code "157") (name "SDA") (class "Default")
      (node (ref "J14") (pin "5") (pinfunction "5_5") (pintype "bidirectional"))
      (node (ref "J15") (pin "9") (pinfunction "9_9") (pintype "bidirectional"))
      (node (ref "J18") (pin "10") (pinfunction "10_10") (pintype "bidirectional"))
      (node (ref "JP2") (pin "5") (pinfunction "5_5") (pintype "passive"))
      (node (ref "JP4") (pin "4") (pinfunction "4_4") (pintype "passive"))
      (node (ref "QWIIC1") (pin "3") (pinfunction "SDA_3") (pintype "passive"))
      (node (ref "R29") (pin "1") (pinfunction "1_1") (pintype "passive"))
    )
    (net (code "158") (name "UART0_RX") (class "Default")
      (node (ref "J12") (pin "3") (pinfunction "3_3") (pintype "passive"))
      (node (ref "J16") (pin "19") (pinfunction "19_19") (pintype "bidirectional"))
    )
    (net (code "159") (name "UART0_TX") (class "Default")
      (node (ref "J12") (pin "1") (pinfunction "1_1") (pintype "passive"))
      (node (ref "J16") (pin "20") (pinfunction "20_20") (pintype "bidirectional"))
    )
    (net (code "160") (name "VBUS") (class "Default")
      (node (ref "D1") (pin "2") (pinfunction "A_2") (pintype "bidirectional"))
      (node (ref "J14") (pin "1") (pinfunction "1_1") (pintype "bidirectional"))
      (node (ref "J16") (pin "1") (pinfunction "1_1") (pintype "bidirectional"))
    )
    (net (code "161") (name "unconnected-(IC7-CD+-Pad10)") (class "Default")
      (node (ref "IC7") (pin "10") (pinfunction "CD+_10") (pintype "passive"))
    )
    (net (code "162") (name "unconnected-(IC8-CD+-Pad10)") (class "Default")
      (node (ref "IC8") (pin "10") (pinfunction "CD+_10") (pintype "passive"))
    )
    (net (code "163") (name "unconnected-(IC9-CD+-Pad10)") (class "Default")
      (node (ref "IC9") (pin "10") (pinfunction "CD+_10") (pintype "passive"))
    )
    (net (code "164") (name "unconnected-(IC10-CD+-Pad10)") (class "Default")
      (node (ref "IC10") (pin "10") (pinfunction "CD+_10") (pintype "passive"))
    )
    (net (code "165") (name "unconnected-(IC11-~{QH}-Pad7)") (class "Default")
      (node (ref "IC11") (pin "7") (pinfunction "~{QH}_7") (pintype "bidirectional"))
    )
    (net (code "166") (name "unconnected-(IC12-~{QH}-Pad7)") (class "Default")
      (node (ref "IC12") (pin "7") (pinfunction "~{QH}_7") (pintype "bidirectional"))
    )
    (net (code "167") (name "unconnected-(IC13-1~{Q}-Pad6)") (class "Default")
      (node (ref "IC13") (pin "6") (pinfunction "1~{Q}_6") (pintype "bidirectional"))
    )
    (net (code "168") (name "unconnected-(IC13-2CLK-Pad11)") (class "Default")
      (node (ref "IC13") (pin "11") (pinfunction "2CLK_11") (pintype "bidirectional"))
    )
    (net (code "169") (name "unconnected-(IC13-2D-Pad12)") (class "Default")
      (node (ref "IC13") (pin "12") (pinfunction "2D_12") (pintype "bidirectional"))
    )
    (net (code "170") (name "unconnected-(IC13-2Q-Pad9)") (class "Default")
      (node (ref "IC13") (pin "9") (pinfunction "2Q_9") (pintype "bidirectional"))
    )
    (net (code "171") (name "unconnected-(IC13-2~{CLR}-Pad13)") (class "Default")
      (node (ref "IC13") (pin "13") (pinfunction "2~{CLR}_13") (pintype "bidirectional"))
    )
    (net (code "172") (name "unconnected-(IC13-2~{PRE}-Pad10)") (class "Default")
      (node (ref "IC13") (pin "10") (pinfunction "2~{PRE}_10") (pintype "bidirectional"))
    )
    (net (code "173") (name "unconnected-(IC13-2~{Q}-Pad8)") (class "Default")
      (node (ref "IC13") (pin "8") (pinfunction "2~{Q}_8") (pintype "bidirectional"))
    )
    (net (code "174") (name "unconnected-(IC16-~{QH}-Pad7)") (class "Default")
      (node (ref "IC16") (pin "7") (pinfunction "~{QH}_7") (pintype "bidirectional"))
    )
    (net (code "175") (name "unconnected-(IC18-SER-Pad10)") (class "Default")
      (node (ref "IC18") (pin "10") (pinfunction "SER_10") (pintype "bidirectional"))
    )
    (net (code "176") (name "unconnected-(IC18-~{QH}-Pad7)") (class "Default")
      (node (ref "IC18") (pin "7") (pinfunction "~{QH}_7") (pintype "bidirectional"))
    )
    (net (code "177") (name "unconnected-(J3-Pad2)") (class "Default")
      (node (ref "J3") (pin "2") (pinfunction "2_2") (pintype "bidirectional"))
    )
    (net (code "178") (name "unconnected-(J4-Pad2)") (class "Default")
      (node (ref "J4") (pin "2") (pinfunction "2_2") (pintype "bidirectional"))
    )
    (net (code "179") (name "unconnected-(J5-Pad6)") (class "Default")
      (node (ref "J5") (pin "6") (pinfunction "6_6") (pintype "bidirectional"))
    )
    (net (code "180") (name "unconnected-(J6-Pad5)") (class "Default")
      (node (ref "J6") (pin "5") (pinfunction "5_5") (pintype "bidirectional"))
    )
    (net (code "181") (name "unconnected-(J7-Pad4)") (class "Default")
      (node (ref "J7") (pin "4") (pinfunction "4_4") (pintype "bidirectional"))
    )
    (net (code "182") (name "unconnected-(J8-Pad3)") (class "Default")
      (node (ref "J8") (pin "3") (pinfunction "3_3") (pintype "bidirectional"))
    )
    (net (code "183") (name "unconnected-(J9-Pad7)") (class "Default")
      (node (ref "J9") (pin "7") (pinfunction "7_7") (pintype "bidirectional"))
    )
    (net (code "184") (name "unconnected-(J16-Pad2)") (class "Default")
      (node (ref "J16") (pin "2") (pinfunction "2_2") (pintype "bidirectional"))
    )
    (net (code "185") (name "unconnected-(J16-Pad4)") (class "Default")
      (node (ref "J16") (pin "4") (pinfunction "4_4") (pintype "bidirectional"))
    )
    (net (code "186") (name "unconnected-(J16-Pad6)") (class "Default")
      (node (ref "J16") (pin "6") (pinfunction "6_6") (pintype "bidirectional"))
    )
    (net (code "187") (name "unconnected-(J16-Pad14)") (class "Default")
      (node (ref "J16") (pin "14") (pinfunction "14_14") (pintype "bidirectional"))
    )
    (net (code "188") (name "unconnected-(J18-Pad1)") (class "Default")
      (node (ref "J18") (pin "1") (pinfunction "1_1") (pintype "bidirectional"))
    )
    (net (code "189") (name "unconnected-(J18-Pad4)") (class "Default")
      (node (ref "J18") (pin "4") (pinfunction "4_4") (pintype "bidirectional"))
    )
    (net (code "190") (name "unconnected-(J18-Pad6)") (class "Default")
      (node (ref "J18") (pin "6") (pinfunction "6_6") (pintype "bidirectional"))
    )
    (net (code "191") (name "unconnected-(JP1-Pad1)") (class "Default")
      (node (ref "JP1") (pin "1") (pinfunction "1_1") (pintype "passive"))
    )
    (net (code "192") (name "unconnected-(JP1-Pad2)") (class "Default")
      (node (ref "JP1") (pin "2") (pinfunction "2_2") (pintype "passive"))
    )
    (net (code "193") (name "unconnected-(JP1-Pad3)") (class "Default")
      (node (ref "JP1") (pin "3") (pinfunction "3_3") (pintype "passive"))
    )
    (net (code "194") (name "unconnected-(JP1-Pad4)") (class "Default")
      (node (ref "JP1") (pin "4") (pinfunction "4_4") (pintype "passive"))
    )
    (net (code "195") (name "unconnected-(JP1-Pad5)") (class "Default")
      (node (ref "JP1") (pin "5") (pinfunction "5_5") (pintype "passive"))
    )
    (net (code "196") (name "unconnected-(JP2-Pad2)") (class "Default")
      (node (ref "JP2") (pin "2") (pinfunction "2_2") (pintype "passive"))
    )
    (net (code "197") (name "unconnected-(JP3-Pad1)") (class "Default")
      (node (ref "JP3") (pin "1") (pinfunction "1_1") (pintype "passive"))
    )
    (net (code "198") (name "unconnected-(JP3-Pad3)") (class "Default")
      (node (ref "JP3") (pin "3") (pinfunction "3_3") (pintype "passive"))
    )
    (net (code "199") (name "unconnected-(JP3-Pad4)") (class "Default")
      (node (ref "JP3") (pin "4") (pinfunction "4_4") (pintype "passive"))
    )
    (net (code "200") (name "unconnected-(JP3-Pad6)") (class "Default")
      (node (ref "JP3") (pin "6") (pinfunction "6_6") (pintype "passive"))
    )
    (net (code "201") (name "{slash}PERIPHERAL_POWER_ENABLE") (class "Default")
      (node (ref "J14") (pin "7") (pinfunction "7_7") (pintype "bidirectional"))
      (node (ref "J15") (pin "7") (pinfunction "7_7") (pintype "bidirectional"))
      (node (ref "R26") (pin "1") (pinfunction "1_1") (pintype "passive"))
      (node (ref "R28") (pin "1") (pinfunction "1_1") (pintype "passive"))
      (node (ref "R33") (pin "1") (pinfunction "1_1") (pintype "passive"))
    )
  )
)
